# ccnor_stm32_v25-sync-unified-mini_panels.net
KiCad netlist of a schematic drawn in EAGLE
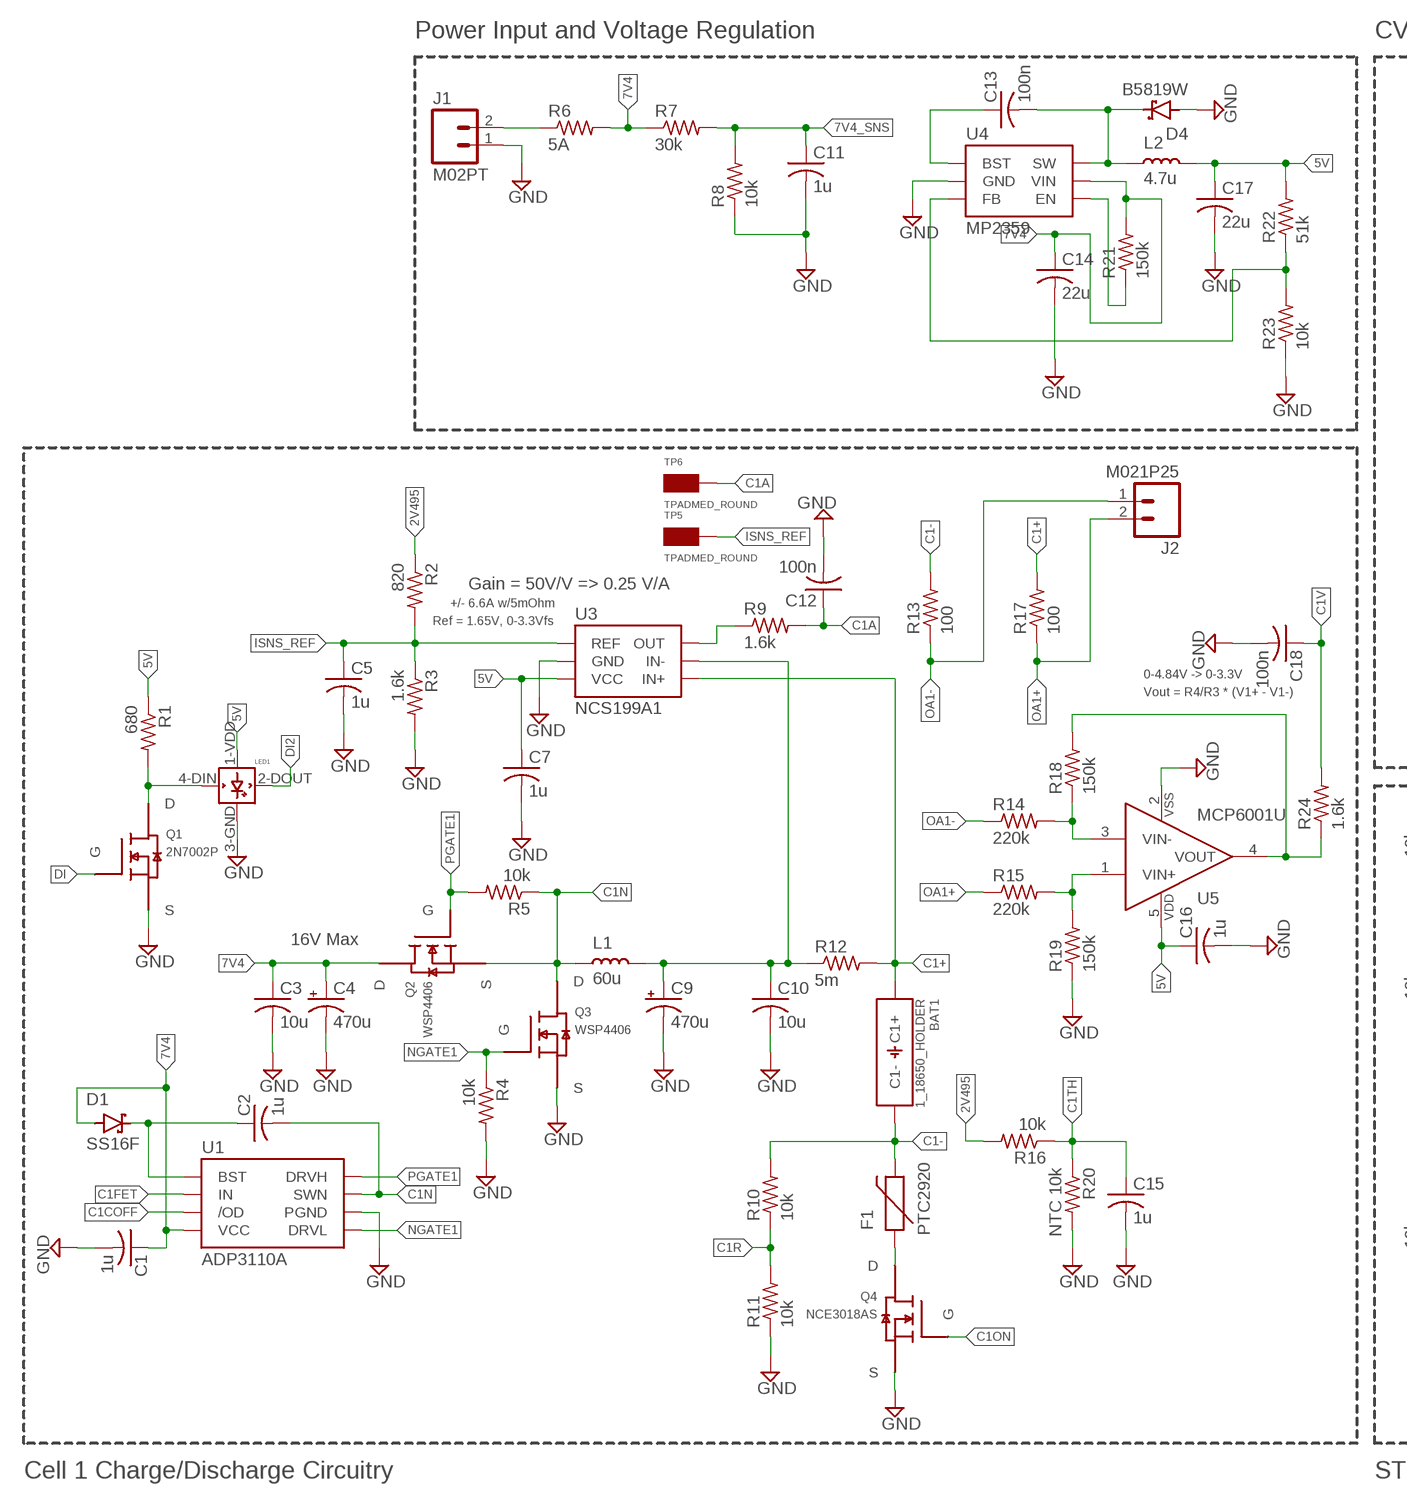
[diagram p0: schematic, sheet 1, part 1 of 3]
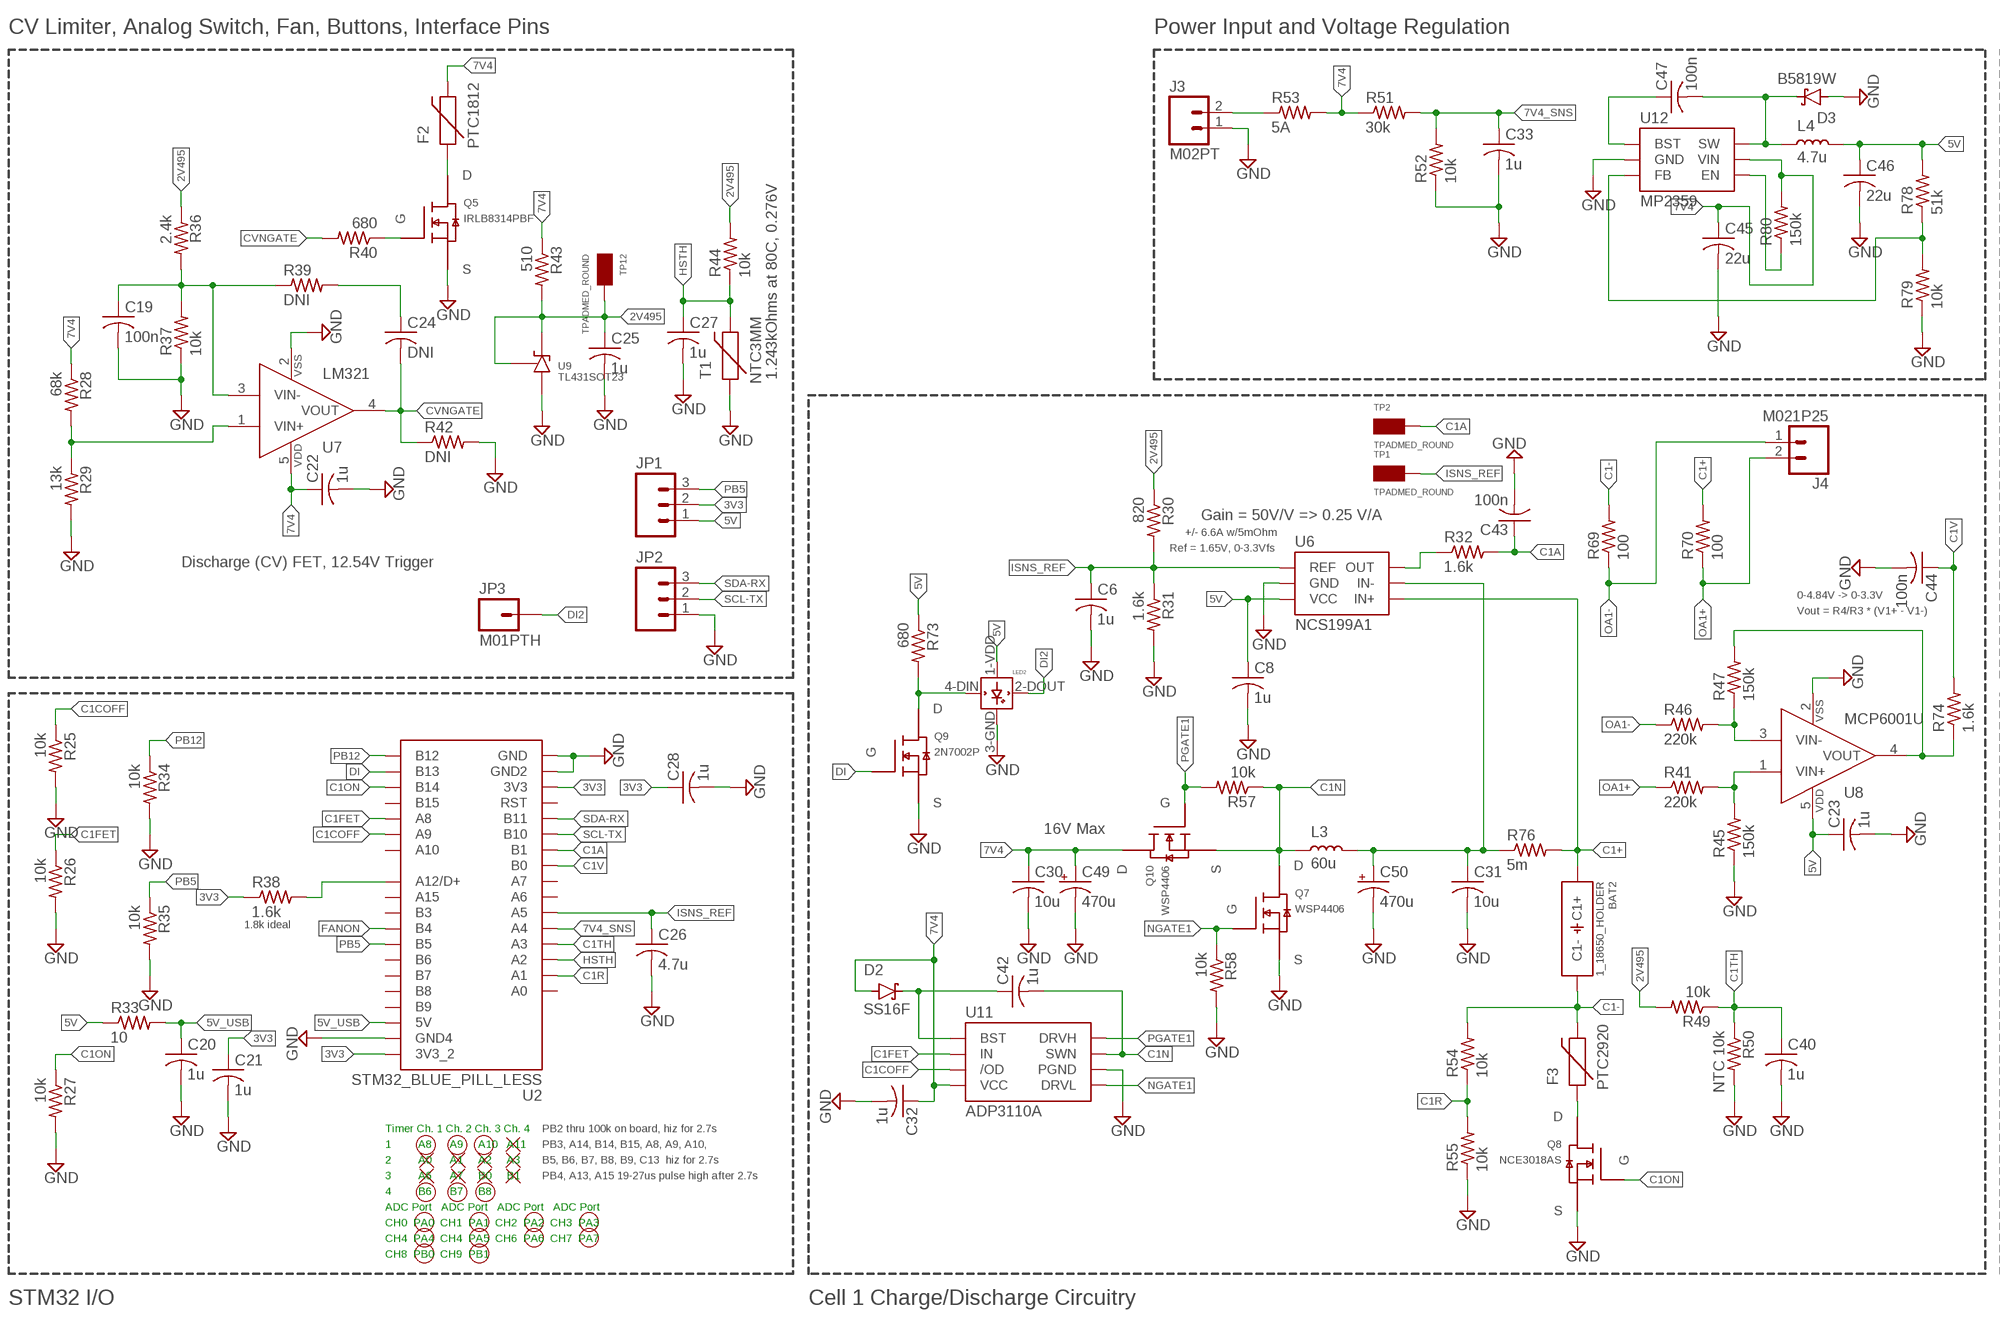
[diagram p1: schematic, sheet 1, part 2 of 3]
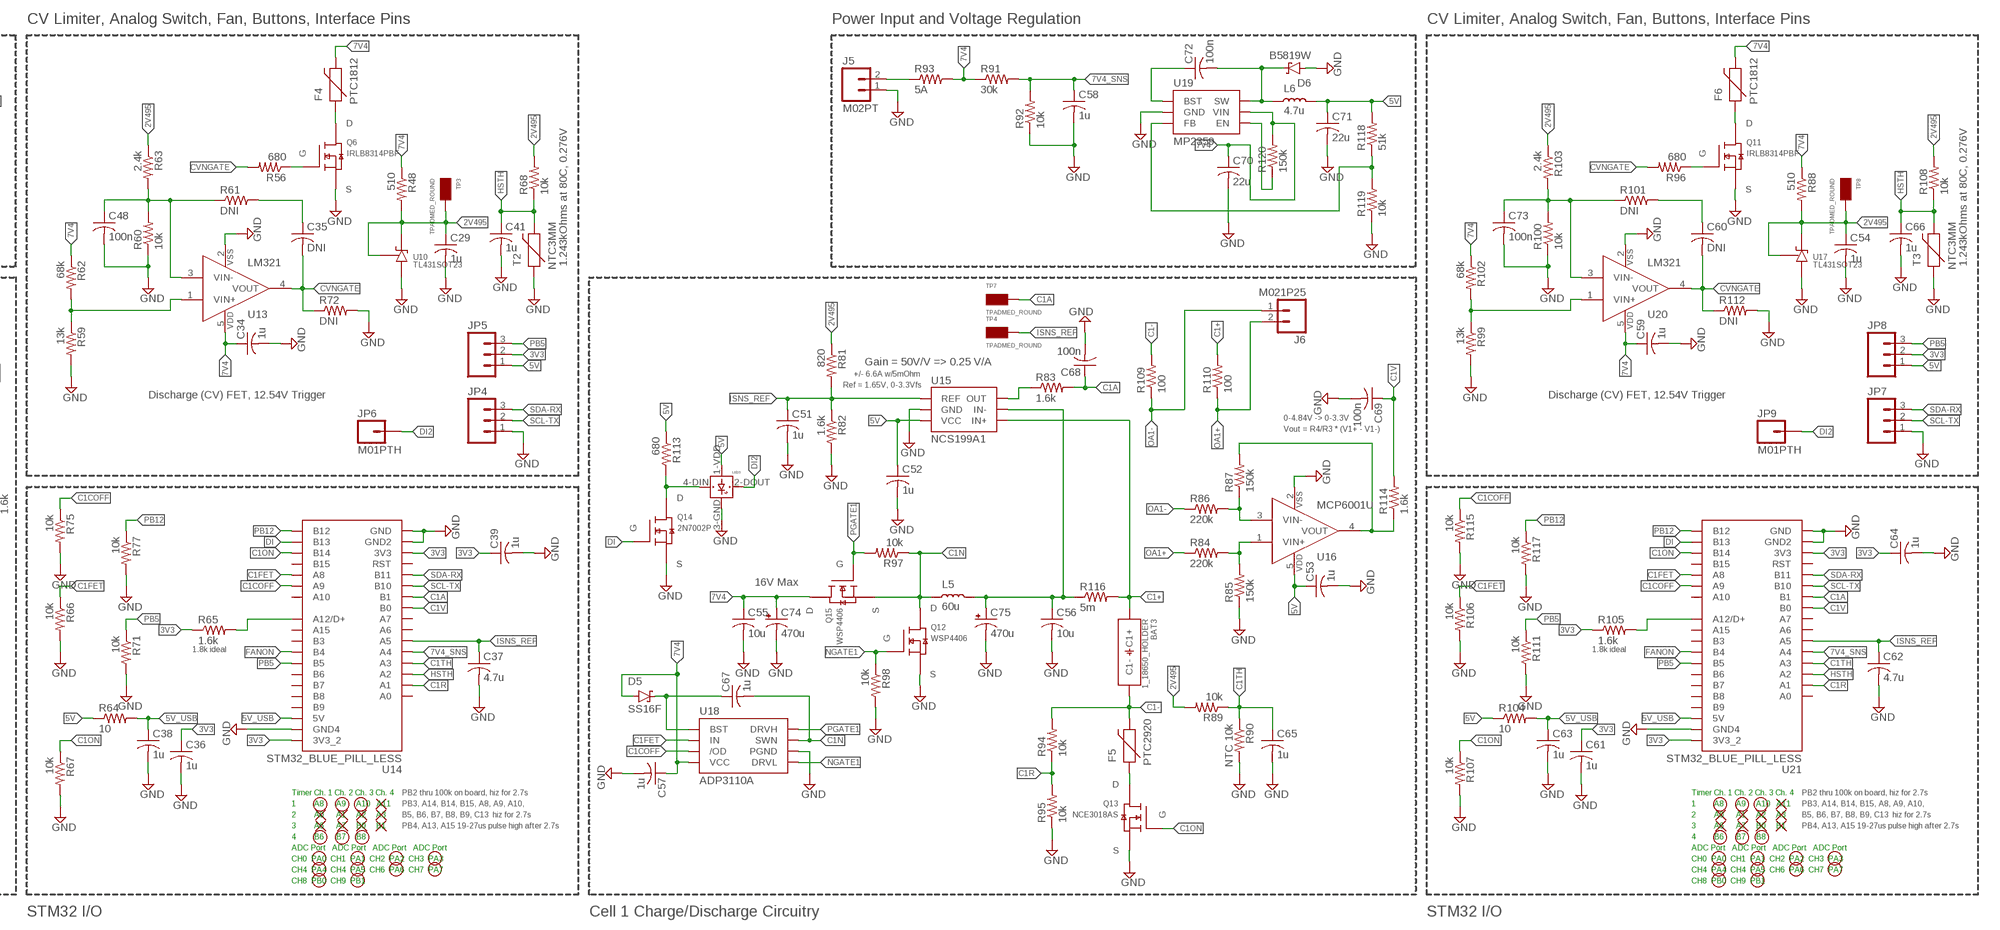
[diagram p2: schematic, sheet 1, part 3 of 3]

(export (version "E")
  (design (tool "Eeschema 10.0.6"))
  (components
    (comp (ref "BAT1")
      (value "1_18650_HOLDER")
      (footprint "eagle-import:1S_18650_SMD_NH")
      (libsource (lib "eagle-import") (part "1_18650_HOLDER"))
    )
    (comp (ref "BAT2")
      (value "1_18650_HOLDER")
      (footprint "eagle-import:1S_18650_SMD_NH")
      (libsource (lib "eagle-import") (part "1_18650_HOLDER"))
    )
    (comp (ref "BAT3")
      (value "1_18650_HOLDER")
      (footprint "eagle-import:1S_18650_SMD_NH")
      (libsource (lib "eagle-import") (part "1_18650_HOLDER"))
    )
    (comp (ref "C1")
      (value "1u")
      (footprint "eagle-import:C0402")
      (libsource (lib "eagle-import") (part "C-USC0402"))
    )
    (comp (ref "C2")
      (value "1u")
      (footprint "eagle-import:C0603")
      (libsource (lib "eagle-import") (part "C-USC0603"))
    )
    (comp (ref "C3")
      (value "10u")
      (footprint "eagle-import:C1206")
      (libsource (lib "eagle-import") (part "C-USC1206"))
    )
    (comp (ref "C4")
      (value "470u")
      (footprint "eagle-import:E2,5-7")
      (libsource (lib "eagle-import") (part "CPOL-USE2.5-7"))
    )
    (comp (ref "C5")
      (value "1u")
      (footprint "eagle-import:C0402")
      (libsource (lib "eagle-import") (part "C-USC0402"))
    )
    (comp (ref "C6")
      (value "1u")
      (footprint "eagle-import:C0402")
      (libsource (lib "eagle-import") (part "C-USC0402"))
    )
    (comp (ref "C7")
      (value "1u")
      (footprint "eagle-import:C0402")
      (libsource (lib "eagle-import") (part "C-USC0402"))
    )
    (comp (ref "C8")
      (value "1u")
      (footprint "eagle-import:C0402")
      (libsource (lib "eagle-import") (part "C-USC0402"))
    )
    (comp (ref "C9")
      (value "470u")
      (footprint "eagle-import:E2,5-7")
      (libsource (lib "eagle-import") (part "CPOL-USE2.5-7"))
    )
    (comp (ref "C10")
      (value "10u")
      (footprint "eagle-import:C1206")
      (libsource (lib "eagle-import") (part "C-USC1206"))
    )
    (comp (ref "C11")
      (value "1u")
      (footprint "eagle-import:C0402")
      (libsource (lib "eagle-import") (part "C-USC0402"))
    )
    (comp (ref "C12")
      (value "100n")
      (footprint "eagle-import:C0402")
      (libsource (lib "eagle-import") (part "C-USC0402"))
    )
    (comp (ref "C13")
      (value "100n")
      (footprint "eagle-import:C0402")
      (libsource (lib "eagle-import") (part "C-USC0402"))
    )
    (comp (ref "C14")
      (value "22u")
      (footprint "eagle-import:C0805")
      (libsource (lib "eagle-import") (part "C-USC0805"))
    )
    (comp (ref "C15")
      (value "1u")
      (footprint "eagle-import:C0402")
      (libsource (lib "eagle-import") (part "C-USC0402"))
    )
    (comp (ref "C16")
      (value "1u")
      (footprint "eagle-import:C0402")
      (libsource (lib "eagle-import") (part "C-USC0402"))
    )
    (comp (ref "C17")
      (value "22u")
      (footprint "eagle-import:C0603")
      (libsource (lib "eagle-import") (part "C-USC0603"))
    )
    (comp (ref "C18")
      (value "100n")
      (footprint "eagle-import:C0402")
      (libsource (lib "eagle-import") (part "C-USC0402"))
    )
    (comp (ref "C19")
      (value "100n")
      (footprint "eagle-import:C0402")
      (libsource (lib "eagle-import") (part "C-USC0402"))
    )
    (comp (ref "C20")
      (value "1u")
      (footprint "eagle-import:C0402")
      (libsource (lib "eagle-import") (part "C-USC0402"))
    )
    (comp (ref "C21")
      (value "1u")
      (footprint "eagle-import:C0402")
      (libsource (lib "eagle-import") (part "C-USC0402"))
    )
    (comp (ref "C22")
      (value "1u")
      (footprint "eagle-import:C0402")
      (libsource (lib "eagle-import") (part "C-USC0402"))
    )
    (comp (ref "C23")
      (value "1u")
      (footprint "eagle-import:C0402")
      (libsource (lib "eagle-import") (part "C-USC0402"))
    )
    (comp (ref "C24")
      (value "DNI")
      (footprint "eagle-import:C0402")
      (libsource (lib "eagle-import") (part "C-USC0402"))
    )
    (comp (ref "C25")
      (value "1u")
      (footprint "eagle-import:C0402")
      (libsource (lib "eagle-import") (part "C-USC0402"))
    )
    (comp (ref "C26")
      (value "4.7u")
      (footprint "eagle-import:C0402")
      (libsource (lib "eagle-import") (part "C-USC0402"))
    )
    (comp (ref "C27")
      (value "1u")
      (footprint "eagle-import:C0402")
      (libsource (lib "eagle-import") (part "C-USC0402"))
    )
    (comp (ref "C28")
      (value "1u")
      (footprint "eagle-import:C0402")
      (libsource (lib "eagle-import") (part "C-USC0402"))
    )
    (comp (ref "C29")
      (value "1u")
      (footprint "eagle-import:C0402")
      (libsource (lib "eagle-import") (part "C-USC0402"))
    )
    (comp (ref "C30")
      (value "10u")
      (footprint "eagle-import:C1206")
      (libsource (lib "eagle-import") (part "C-USC1206"))
    )
    (comp (ref "C31")
      (value "10u")
      (footprint "eagle-import:C1206")
      (libsource (lib "eagle-import") (part "C-USC1206"))
    )
    (comp (ref "C32")
      (value "1u")
      (footprint "eagle-import:C0402")
      (libsource (lib "eagle-import") (part "C-USC0402"))
    )
    (comp (ref "C33")
      (value "1u")
      (footprint "eagle-import:C0402")
      (libsource (lib "eagle-import") (part "C-USC0402"))
    )
    (comp (ref "C34")
      (value "1u")
      (footprint "eagle-import:C0402")
      (libsource (lib "eagle-import") (part "C-USC0402"))
    )
    (comp (ref "C35")
      (value "DNI")
      (footprint "eagle-import:C0402")
      (libsource (lib "eagle-import") (part "C-USC0402"))
    )
    (comp (ref "C36")
      (value "1u")
      (footprint "eagle-import:C0402")
      (libsource (lib "eagle-import") (part "C-USC0402"))
    )
    (comp (ref "C37")
      (value "4.7u")
      (footprint "eagle-import:C0402")
      (libsource (lib "eagle-import") (part "C-USC0402"))
    )
    (comp (ref "C38")
      (value "1u")
      (footprint "eagle-import:C0402")
      (libsource (lib "eagle-import") (part "C-USC0402"))
    )
    (comp (ref "C39")
      (value "1u")
      (footprint "eagle-import:C0402")
      (libsource (lib "eagle-import") (part "C-USC0402"))
    )
    (comp (ref "C40")
      (value "1u")
      (footprint "eagle-import:C0402")
      (libsource (lib "eagle-import") (part "C-USC0402"))
    )
    (comp (ref "C41")
      (value "1u")
      (footprint "eagle-import:C0402")
      (libsource (lib "eagle-import") (part "C-USC0402"))
    )
    (comp (ref "C42")
      (value "1u")
      (footprint "eagle-import:C0603")
      (libsource (lib "eagle-import") (part "C-USC0603"))
    )
    (comp (ref "C43")
      (value "100n")
      (footprint "eagle-import:C0402")
      (libsource (lib "eagle-import") (part "C-USC0402"))
    )
    (comp (ref "C44")
      (value "100n")
      (footprint "eagle-import:C0402")
      (libsource (lib "eagle-import") (part "C-USC0402"))
    )
    (comp (ref "C45")
      (value "22u")
      (footprint "eagle-import:C0805")
      (libsource (lib "eagle-import") (part "C-USC0805"))
    )
    (comp (ref "C46")
      (value "22u")
      (footprint "eagle-import:C0603")
      (libsource (lib "eagle-import") (part "C-USC0603"))
    )
    (comp (ref "C47")
      (value "100n")
      (footprint "eagle-import:C0402")
      (libsource (lib "eagle-import") (part "C-USC0402"))
    )
    (comp (ref "C48")
      (value "100n")
      (footprint "eagle-import:C0402")
      (libsource (lib "eagle-import") (part "C-USC0402"))
    )
    (comp (ref "C49")
      (value "470u")
      (footprint "eagle-import:E2,5-7")
      (libsource (lib "eagle-import") (part "CPOL-USE2.5-7"))
    )
    (comp (ref "C50")
      (value "470u")
      (footprint "eagle-import:E2,5-7")
      (libsource (lib "eagle-import") (part "CPOL-USE2.5-7"))
    )
    (comp (ref "C51")
      (value "1u")
      (footprint "eagle-import:C0402")
      (libsource (lib "eagle-import") (part "C-USC0402"))
    )
    (comp (ref "C52")
      (value "1u")
      (footprint "eagle-import:C0402")
      (libsource (lib "eagle-import") (part "C-USC0402"))
    )
    (comp (ref "C53")
      (value "1u")
      (footprint "eagle-import:C0402")
      (libsource (lib "eagle-import") (part "C-USC0402"))
    )
    (comp (ref "C54")
      (value "1u")
      (footprint "eagle-import:C0402")
      (libsource (lib "eagle-import") (part "C-USC0402"))
    )
    (comp (ref "C55")
      (value "10u")
      (footprint "eagle-import:C1206")
      (libsource (lib "eagle-import") (part "C-USC1206"))
    )
    (comp (ref "C56")
      (value "10u")
      (footprint "eagle-import:C1206")
      (libsource (lib "eagle-import") (part "C-USC1206"))
    )
    (comp (ref "C57")
      (value "1u")
      (footprint "eagle-import:C0402")
      (libsource (lib "eagle-import") (part "C-USC0402"))
    )
    (comp (ref "C58")
      (value "1u")
      (footprint "eagle-import:C0402")
      (libsource (lib "eagle-import") (part "C-USC0402"))
    )
    (comp (ref "C59")
      (value "1u")
      (footprint "eagle-import:C0402")
      (libsource (lib "eagle-import") (part "C-USC0402"))
    )
    (comp (ref "C60")
      (value "DNI")
      (footprint "eagle-import:C0402")
      (libsource (lib "eagle-import") (part "C-USC0402"))
    )
    (comp (ref "C61")
      (value "1u")
      (footprint "eagle-import:C0402")
      (libsource (lib "eagle-import") (part "C-USC0402"))
    )
    (comp (ref "C62")
      (value "4.7u")
      (footprint "eagle-import:C0402")
      (libsource (lib "eagle-import") (part "C-USC0402"))
    )
    (comp (ref "C63")
      (value "1u")
      (footprint "eagle-import:C0402")
      (libsource (lib "eagle-import") (part "C-USC0402"))
    )
    (comp (ref "C64")
      (value "1u")
      (footprint "eagle-import:C0402")
      (libsource (lib "eagle-import") (part "C-USC0402"))
    )
    (comp (ref "C65")
      (value "1u")
      (footprint "eagle-import:C0402")
      (libsource (lib "eagle-import") (part "C-USC0402"))
    )
    (comp (ref "C66")
      (value "1u")
      (footprint "eagle-import:C0402")
      (libsource (lib "eagle-import") (part "C-USC0402"))
    )
    (comp (ref "C67")
      (value "1u")
      (footprint "eagle-import:C0603")
      (libsource (lib "eagle-import") (part "C-USC0603"))
    )
    (comp (ref "C68")
      (value "100n")
      (footprint "eagle-import:C0402")
      (libsource (lib "eagle-import") (part "C-USC0402"))
    )
    (comp (ref "C69")
      (value "100n")
      (footprint "eagle-import:C0402")
      (libsource (lib "eagle-import") (part "C-USC0402"))
    )
    (comp (ref "C70")
      (value "22u")
      (footprint "eagle-import:C0805")
      (libsource (lib "eagle-import") (part "C-USC0805"))
    )
    (comp (ref "C71")
      (value "22u")
      (footprint "eagle-import:C0603")
      (libsource (lib "eagle-import") (part "C-USC0603"))
    )
    (comp (ref "C72")
      (value "100n")
      (footprint "eagle-import:C0402")
      (libsource (lib "eagle-import") (part "C-USC0402"))
    )
    (comp (ref "C73")
      (value "100n")
      (footprint "eagle-import:C0402")
      (libsource (lib "eagle-import") (part "C-USC0402"))
    )
    (comp (ref "C74")
      (value "470u")
      (footprint "eagle-import:E2,5-7")
      (libsource (lib "eagle-import") (part "CPOL-USE2.5-7"))
    )
    (comp (ref "C75")
      (value "470u")
      (footprint "eagle-import:E2,5-7")
      (libsource (lib "eagle-import") (part "CPOL-USE2.5-7"))
    )
    (comp (ref "D1")
      (value "SS16F")
      (footprint "eagle-import:SOD123")
      (libsource (lib "eagle-import") (part "DIODE_SCHOTTKYCDBM140-G"))
    )
    (comp (ref "D2")
      (value "SS16F")
      (footprint "eagle-import:SOD123")
      (libsource (lib "eagle-import") (part "DIODE_SCHOTTKYCDBM140-G"))
    )
    (comp (ref "D3")
      (value "B5819W")
      (footprint "eagle-import:SOD123W")
      (libsource (lib "eagle-import") (part "PMEG3020ER"))
    )
    (comp (ref "D4")
      (value "B5819W")
      (footprint "eagle-import:SOD123W")
      (libsource (lib "eagle-import") (part "PMEG3020ER"))
    )
    (comp (ref "D5")
      (value "SS16F")
      (footprint "eagle-import:SOD123")
      (libsource (lib "eagle-import") (part "DIODE_SCHOTTKYCDBM140-G"))
    )
    (comp (ref "D6")
      (value "B5819W")
      (footprint "eagle-import:SOD123W")
      (libsource (lib "eagle-import") (part "PMEG3020ER"))
    )
    (comp (ref "F1")
      (value "PTC2920")
      (footprint "eagle-import:2920")
      (libsource (lib "eagle-import") (part "PTC2920"))
    )
    (comp (ref "F2")
      (value "PTC1812")
      (footprint "eagle-import:1812")
      (libsource (lib "eagle-import") (part "PTC1812"))
    )
    (comp (ref "F3")
      (value "PTC2920")
      (footprint "eagle-import:2920")
      (libsource (lib "eagle-import") (part "PTC2920"))
    )
    (comp (ref "F4")
      (value "PTC1812")
      (footprint "eagle-import:1812")
      (libsource (lib "eagle-import") (part "PTC1812"))
    )
    (comp (ref "F5")
      (value "PTC2920")
      (footprint "eagle-import:2920")
      (libsource (lib "eagle-import") (part "PTC2920"))
    )
    (comp (ref "F6")
      (value "PTC1812")
      (footprint "eagle-import:1812")
      (libsource (lib "eagle-import") (part "PTC1812"))
    )
    (comp (ref "J1")
      (value "M02PT")
      (footprint "eagle-import:PHOENIXCONTACT1935161")
      (libsource (lib "eagle-import") (part "M02PT"))
    )
    (comp (ref "J2")
      (value "M021P25")
      (footprint "eagle-import:M02_1P25MM")
      (libsource (lib "eagle-import") (part "M021P25"))
    )
    (comp (ref "J3")
      (value "M02PT")
      (footprint "eagle-import:PHOENIXCONTACT1935161")
      (libsource (lib "eagle-import") (part "M02PT"))
    )
    (comp (ref "J4")
      (value "M021P25")
      (footprint "eagle-import:M02_1P25MM")
      (libsource (lib "eagle-import") (part "M021P25"))
    )
    (comp (ref "J5")
      (value "M02PT")
      (footprint "eagle-import:PHOENIXCONTACT1935161")
      (libsource (lib "eagle-import") (part "M02PT"))
    )
    (comp (ref "J6")
      (value "M021P25")
      (footprint "eagle-import:M02_1P25MM")
      (libsource (lib "eagle-import") (part "M021P25"))
    )
    (comp (ref "JP1")
      (value "M03PTH")
      (footprint "eagle-import:1X03")
      (libsource (lib "eagle-import") (part "M03PTH"))
    )
    (comp (ref "JP2")
      (value "M03PTH")
      (footprint "eagle-import:1X03")
      (libsource (lib "eagle-import") (part "M03PTH"))
    )
    (comp (ref "JP3")
      (value "M01PTH")
      (footprint "eagle-import:1X01")
      (libsource (lib "eagle-import") (part "M01PTH"))
    )
    (comp (ref "JP4")
      (value "M03PTH")
      (footprint "eagle-import:1X03")
      (libsource (lib "eagle-import") (part "M03PTH"))
    )
    (comp (ref "JP5")
      (value "M03PTH")
      (footprint "eagle-import:1X03")
      (libsource (lib "eagle-import") (part "M03PTH"))
    )
    (comp (ref "JP6")
      (value "M01PTH")
      (footprint "eagle-import:1X01")
      (libsource (lib "eagle-import") (part "M01PTH"))
    )
    (comp (ref "JP7")
      (value "M03PTH")
      (footprint "eagle-import:1X03")
      (libsource (lib "eagle-import") (part "M03PTH"))
    )
    (comp (ref "JP8")
      (value "M03PTH")
      (footprint "eagle-import:1X03")
      (libsource (lib "eagle-import") (part "M03PTH"))
    )
    (comp (ref "JP9")
      (value "M01PTH")
      (footprint "eagle-import:1X01")
      (libsource (lib "eagle-import") (part "M01PTH"))
    )
    (comp (ref "L1")
      (value "60u")
      (footprint "eagle-import:INDUCTOR_10A_8.2MMX21MM")
      (libsource (lib "eagle-import") (part "INDUCTOR10A"))
    )
    (comp (ref "L2")
      (value "4.7u")
      (footprint "eagle-import:0805")
      (libsource (lib "eagle-import") (part "INDUCTOR0805"))
    )
    (comp (ref "L3")
      (value "60u")
      (footprint "eagle-import:INDUCTOR_10A_8.2MMX21MM")
      (libsource (lib "eagle-import") (part "INDUCTOR10A"))
    )
    (comp (ref "L4")
      (value "4.7u")
      (footprint "eagle-import:0805")
      (libsource (lib "eagle-import") (part "INDUCTOR0805"))
    )
    (comp (ref "L5")
      (value "60u")
      (footprint "eagle-import:INDUCTOR_10A_8.2MMX21MM")
      (libsource (lib "eagle-import") (part "INDUCTOR10A"))
    )
    (comp (ref "L6")
      (value "4.7u")
      (footprint "eagle-import:0805")
      (libsource (lib "eagle-import") (part "INDUCTOR0805"))
    )
    (comp (ref "LED1")
      (value "WS2812B")
      (footprint "eagle-import:WS2812B")
      (libsource (lib "eagle-import") (part "WS2812B"))
    )
    (comp (ref "LED2")
      (value "WS2812B")
      (footprint "eagle-import:WS2812B")
      (libsource (lib "eagle-import") (part "WS2812B"))
    )
    (comp (ref "LED3")
      (value "WS2812B")
      (footprint "eagle-import:WS2812B")
      (libsource (lib "eagle-import") (part "WS2812B"))
    )
    (comp (ref "Q1")
      (value "2N7002P")
      (footprint "eagle-import:SOT23")
      (libsource (lib "eagle-import") (part "2N7002P"))
    )
    (comp (ref "Q2")
      (value "WSP4406")
      (footprint "eagle-import:8-SOIC")
      (libsource (lib "eagle-import") (part "N-MOSFET-SOIC8"))
    )
    (comp (ref "Q3")
      (value "WSP4406")
      (footprint "eagle-import:8-SOIC")
      (libsource (lib "eagle-import") (part "N-MOSFET-SOIC8"))
    )
    (comp (ref "Q4")
      (value "NCE3018AS")
      (footprint "eagle-import:8-SOIC")
      (libsource (lib "eagle-import") (part "N-MOSFET-SOIC8"))
    )
    (comp (ref "Q5")
      (value "IRLB8314PBF")
      (footprint "eagle-import:TO-220")
      (libsource (lib "eagle-import") (part "IRLB8314PBF"))
    )
    (comp (ref "Q6")
      (value "IRLB8314PBF")
      (footprint "eagle-import:TO-220")
      (libsource (lib "eagle-import") (part "IRLB8314PBF"))
    )
    (comp (ref "Q7")
      (value "WSP4406")
      (footprint "eagle-import:8-SOIC")
      (libsource (lib "eagle-import") (part "N-MOSFET-SOIC8"))
    )
    (comp (ref "Q8")
      (value "NCE3018AS")
      (footprint "eagle-import:8-SOIC")
      (libsource (lib "eagle-import") (part "N-MOSFET-SOIC8"))
    )
    (comp (ref "Q9")
      (value "2N7002P")
      (footprint "eagle-import:SOT23")
      (libsource (lib "eagle-import") (part "2N7002P"))
    )
    (comp (ref "Q10")
      (value "WSP4406")
      (footprint "eagle-import:8-SOIC")
      (libsource (lib "eagle-import") (part "N-MOSFET-SOIC8"))
    )
    (comp (ref "Q11")
      (value "IRLB8314PBF")
      (footprint "eagle-import:TO-220")
      (libsource (lib "eagle-import") (part "IRLB8314PBF"))
    )
    (comp (ref "Q12")
      (value "WSP4406")
      (footprint "eagle-import:8-SOIC")
      (libsource (lib "eagle-import") (part "N-MOSFET-SOIC8"))
    )
    (comp (ref "Q13")
      (value "NCE3018AS")
      (footprint "eagle-import:8-SOIC")
      (libsource (lib "eagle-import") (part "N-MOSFET-SOIC8"))
    )
    (comp (ref "Q14")
      (value "2N7002P")
      (footprint "eagle-import:SOT23")
      (libsource (lib "eagle-import") (part "2N7002P"))
    )
    (comp (ref "Q15")
      (value "WSP4406")
      (footprint "eagle-import:8-SOIC")
      (libsource (lib "eagle-import") (part "N-MOSFET-SOIC8"))
    )
    (comp (ref "R1")
      (value "680")
      (footprint "eagle-import:R0402")
      (libsource (lib "eagle-import") (part "R-US_R0402"))
    )
    (comp (ref "R2")
      (value "820")
      (footprint "eagle-import:R0402")
      (libsource (lib "eagle-import") (part "R-US_R0402"))
    )
    (comp (ref "R3")
      (value "1.6k")
      (footprint "eagle-import:R0402")
      (libsource (lib "eagle-import") (part "R-US_R0402"))
    )
    (comp (ref "R4")
      (value "10k")
      (footprint "eagle-import:R0402")
      (libsource (lib "eagle-import") (part "R-US_R0402"))
    )
    (comp (ref "R5")
      (value "10k")
      (footprint "eagle-import:R0402")
      (libsource (lib "eagle-import") (part "R-US_R0402"))
    )
    (comp (ref "R6")
      (value "5A")
      (footprint "eagle-import:R1206")
      (libsource (lib "eagle-import") (part "R-US_R1206"))
    )
    (comp (ref "R7")
      (value "30k")
      (footprint "eagle-import:R0402")
      (libsource (lib "eagle-import") (part "R-US_R0402"))
    )
    (comp (ref "R8")
      (value "10k")
      (footprint "eagle-import:R0402")
      (libsource (lib "eagle-import") (part "R-US_R0402"))
    )
    (comp (ref "R9")
      (value "1.6k")
      (footprint "eagle-import:R0402")
      (libsource (lib "eagle-import") (part "R-US_R0402"))
    )
    (comp (ref "R10")
      (value "10k")
      (footprint "eagle-import:R0402")
      (libsource (lib "eagle-import") (part "R-US_R0402"))
    )
    (comp (ref "R11")
      (value "10k")
      (footprint "eagle-import:R0402")
      (libsource (lib "eagle-import") (part "R-US_R0402"))
    )
    (comp (ref "R12")
      (value "5m")
      (footprint "eagle-import:R1206")
      (libsource (lib "eagle-import") (part "R-US_R1206"))
    )
    (comp (ref "R13")
      (value "100")
      (footprint "eagle-import:R0402")
      (libsource (lib "eagle-import") (part "R-US_R0402"))
    )
    (comp (ref "R14")
      (value "220k")
      (footprint "eagle-import:R0402")
      (libsource (lib "eagle-import") (part "R-US_R0402"))
    )
    (comp (ref "R15")
      (value "220k")
      (footprint "eagle-import:R0402")
      (libsource (lib "eagle-import") (part "R-US_R0402"))
    )
    (comp (ref "R16")
      (value "10k")
      (footprint "eagle-import:R0402")
      (libsource (lib "eagle-import") (part "R-US_R0402"))
    )
    (comp (ref "R17")
      (value "100")
      (footprint "eagle-import:R0402")
      (libsource (lib "eagle-import") (part "R-US_R0402"))
    )
    (comp (ref "R18")
      (value "150k")
      (footprint "eagle-import:R0402")
      (libsource (lib "eagle-import") (part "R-US_R0402"))
    )
    (comp (ref "R19")
      (value "150k")
      (footprint "eagle-import:R0402")
      (libsource (lib "eagle-import") (part "R-US_R0402"))
    )
    (comp (ref "R20")
      (value "NTC 10k")
      (footprint "eagle-import:R0402")
      (libsource (lib "eagle-import") (part "R-US_R0402"))
    )
    (comp (ref "R21")
      (value "150k")
      (footprint "eagle-import:R0402")
      (libsource (lib "eagle-import") (part "R-US_R0402"))
    )
    (comp (ref "R22")
      (value "51k")
      (footprint "eagle-import:R0402")
      (libsource (lib "eagle-import") (part "R-US_R0402"))
    )
    (comp (ref "R23")
      (value "10k")
      (footprint "eagle-import:R0402")
      (libsource (lib "eagle-import") (part "R-US_R0402"))
    )
    (comp (ref "R24")
      (value "1.6k")
      (footprint "eagle-import:R0402")
      (libsource (lib "eagle-import") (part "R-US_R0402"))
    )
    (comp (ref "R25")
      (value "10k")
      (footprint "eagle-import:R0402")
      (libsource (lib "eagle-import") (part "R-US_R0402"))
    )
    (comp (ref "R26")
      (value "10k")
      (footprint "eagle-import:R0402")
      (libsource (lib "eagle-import") (part "R-US_R0402"))
    )
    (comp (ref "R27")
      (value "10k")
      (footprint "eagle-import:R0402")
      (libsource (lib "eagle-import") (part "R-US_R0402"))
    )
    (comp (ref "R28")
      (value "68k")
      (footprint "eagle-import:R0402")
      (libsource (lib "eagle-import") (part "R-US_R0402"))
    )
    (comp (ref "R29")
      (value "13k")
      (footprint "eagle-import:R0402")
      (libsource (lib "eagle-import") (part "R-US_R0402"))
    )
    (comp (ref "R30")
      (value "820")
      (footprint "eagle-import:R0402")
      (libsource (lib "eagle-import") (part "R-US_R0402"))
    )
    (comp (ref "R31")
      (value "1.6k")
      (footprint "eagle-import:R0402")
      (libsource (lib "eagle-import") (part "R-US_R0402"))
    )
    (comp (ref "R32")
      (value "1.6k")
      (footprint "eagle-import:R0402")
      (libsource (lib "eagle-import") (part "R-US_R0402"))
    )
    (comp (ref "R33")
      (value "10")
      (footprint "eagle-import:R0402")
      (libsource (lib "eagle-import") (part "R-US_R0402"))
    )
    (comp (ref "R34")
      (value "10k")
      (footprint "eagle-import:R0402")
      (libsource (lib "eagle-import") (part "R-US_R0402"))
    )
    (comp (ref "R35")
      (value "10k")
      (footprint "eagle-import:R0402")
      (libsource (lib "eagle-import") (part "R-US_R0402"))
    )
    (comp (ref "R36")
      (value "2.4k")
      (footprint "eagle-import:R0402")
      (libsource (lib "eagle-import") (part "R-US_R0402"))
    )
    (comp (ref "R37")
      (value "10k")
      (footprint "eagle-import:R0402")
      (libsource (lib "eagle-import") (part "R-US_R0402"))
    )
    (comp (ref "R38")
      (value "1.6k")
      (footprint "eagle-import:R0402")
      (libsource (lib "eagle-import") (part "R-US_R0402"))
    )
    (comp (ref "R39")
      (value "DNI")
      (footprint "eagle-import:R0402")
      (libsource (lib "eagle-import") (part "R-US_R0402"))
    )
    (comp (ref "R40")
      (value "680")
      (footprint "eagle-import:R0402")
      (libsource (lib "eagle-import") (part "R-US_R0402"))
    )
    (comp (ref "R41")
      (value "220k")
      (footprint "eagle-import:R0402")
      (libsource (lib "eagle-import") (part "R-US_R0402"))
    )
    (comp (ref "R42")
      (value "DNI")
      (footprint "eagle-import:R0402")
      (libsource (lib "eagle-import") (part "R-US_R0402"))
    )
    (comp (ref "R43")
      (value "510")
      (footprint "eagle-import:R0402")
      (libsource (lib "eagle-import") (part "R-US_R0402"))
    )
    (comp (ref "R44")
      (value "10k")
      (footprint "eagle-import:R0402")
      (libsource (lib "eagle-import") (part "R-US_R0402"))
    )
    (comp (ref "R45")
      (value "150k")
      (footprint "eagle-import:R0402")
      (libsource (lib "eagle-import") (part "R-US_R0402"))
    )
    (comp (ref "R46")
      (value "220k")
      (footprint "eagle-import:R0402")
      (libsource (lib "eagle-import") (part "R-US_R0402"))
    )
    (comp (ref "R47")
      (value "150k")
      (footprint "eagle-import:R0402")
      (libsource (lib "eagle-import") (part "R-US_R0402"))
    )
    (comp (ref "R48")
      (value "510")
      (footprint "eagle-import:R0402")
      (libsource (lib "eagle-import") (part "R-US_R0402"))
    )
    (comp (ref "R49")
      (value "10k")
      (footprint "eagle-import:R0402")
      (libsource (lib "eagle-import") (part "R-US_R0402"))
    )
    (comp (ref "R50")
      (value "NTC 10k")
      (footprint "eagle-import:R0402")
      (libsource (lib "eagle-import") (part "R-US_R0402"))
    )
    (comp (ref "R51")
      (value "30k")
      (footprint "eagle-import:R0402")
      (libsource (lib "eagle-import") (part "R-US_R0402"))
    )
    (comp (ref "R52")
      (value "10k")
      (footprint "eagle-import:R0402")
      (libsource (lib "eagle-import") (part "R-US_R0402"))
    )
    (comp (ref "R53")
      (value "5A")
      (footprint "eagle-import:R1206")
      (libsource (lib "eagle-import") (part "R-US_R1206"))
    )
    (comp (ref "R54")
      (value "10k")
      (footprint "eagle-import:R0402")
      (libsource (lib "eagle-import") (part "R-US_R0402"))
    )
    (comp (ref "R55")
      (value "10k")
      (footprint "eagle-import:R0402")
      (libsource (lib "eagle-import") (part "R-US_R0402"))
    )
    (comp (ref "R56")
      (value "680")
      (footprint "eagle-import:R0402")
      (libsource (lib "eagle-import") (part "R-US_R0402"))
    )
    (comp (ref "R57")
      (value "10k")
      (footprint "eagle-import:R0402")
      (libsource (lib "eagle-import") (part "R-US_R0402"))
    )
    (comp (ref "R58")
      (value "10k")
      (footprint "eagle-import:R0402")
      (libsource (lib "eagle-import") (part "R-US_R0402"))
    )
    (comp (ref "R59")
      (value "13k")
      (footprint "eagle-import:R0402")
      (libsource (lib "eagle-import") (part "R-US_R0402"))
    )
    (comp (ref "R60")
      (value "10k")
      (footprint "eagle-import:R0402")
      (libsource (lib "eagle-import") (part "R-US_R0402"))
    )
    (comp (ref "R61")
      (value "DNI")
      (footprint "eagle-import:R0402")
      (libsource (lib "eagle-import") (part "R-US_R0402"))
    )
    (comp (ref "R62")
      (value "68k")
      (footprint "eagle-import:R0402")
      (libsource (lib "eagle-import") (part "R-US_R0402"))
    )
    (comp (ref "R63")
      (value "2.4k")
      (footprint "eagle-import:R0402")
      (libsource (lib "eagle-import") (part "R-US_R0402"))
    )
    (comp (ref "R64")
      (value "10")
      (footprint "eagle-import:R0402")
      (libsource (lib "eagle-import") (part "R-US_R0402"))
    )
    (comp (ref "R65")
      (value "1.6k")
      (footprint "eagle-import:R0402")
      (libsource (lib "eagle-import") (part "R-US_R0402"))
    )
    (comp (ref "R66")
      (value "10k")
      (footprint "eagle-import:R0402")
      (libsource (lib "eagle-import") (part "R-US_R0402"))
    )
    (comp (ref "R67")
      (value "10k")
      (footprint "eagle-import:R0402")
      (libsource (lib "eagle-import") (part "R-US_R0402"))
    )
    (comp (ref "R68")
      (value "10k")
      (footprint "eagle-import:R0402")
      (libsource (lib "eagle-import") (part "R-US_R0402"))
    )
    (comp (ref "R69")
      (value "100")
      (footprint "eagle-import:R0402")
      (libsource (lib "eagle-import") (part "R-US_R0402"))
    )
    (comp (ref "R70")
      (value "100")
      (footprint "eagle-import:R0402")
      (libsource (lib "eagle-import") (part "R-US_R0402"))
    )
    (comp (ref "R71")
      (value "10k")
      (footprint "eagle-import:R0402")
      (libsource (lib "eagle-import") (part "R-US_R0402"))
    )
    (comp (ref "R72")
      (value "DNI")
      (footprint "eagle-import:R0402")
      (libsource (lib "eagle-import") (part "R-US_R0402"))
    )
    (comp (ref "R73")
      (value "680")
      (footprint "eagle-import:R0402")
      (libsource (lib "eagle-import") (part "R-US_R0402"))
    )
    (comp (ref "R74")
      (value "1.6k")
      (footprint "eagle-import:R0402")
      (libsource (lib "eagle-import") (part "R-US_R0402"))
    )
    (comp (ref "R75")
      (value "10k")
      (footprint "eagle-import:R0402")
      (libsource (lib "eagle-import") (part "R-US_R0402"))
    )
    (comp (ref "R76")
      (value "5m")
      (footprint "eagle-import:R1206")
      (libsource (lib "eagle-import") (part "R-US_R1206"))
    )
    (comp (ref "R77")
      (value "10k")
      (footprint "eagle-import:R0402")
      (libsource (lib "eagle-import") (part "R-US_R0402"))
    )
    (comp (ref "R78")
      (value "51k")
      (footprint "eagle-import:R0402")
      (libsource (lib "eagle-import") (part "R-US_R0402"))
    )
    (comp (ref "R79")
      (value "10k")
      (footprint "eagle-import:R0402")
      (libsource (lib "eagle-import") (part "R-US_R0402"))
    )
    (comp (ref "R80")
      (value "150k")
      (footprint "eagle-import:R0402")
      (libsource (lib "eagle-import") (part "R-US_R0402"))
    )
    (comp (ref "R81")
      (value "820")
      (footprint "eagle-import:R0402")
      (libsource (lib "eagle-import") (part "R-US_R0402"))
    )
    (comp (ref "R82")
      (value "1.6k")
      (footprint "eagle-import:R0402")
      (libsource (lib "eagle-import") (part "R-US_R0402"))
    )
    (comp (ref "R83")
      (value "1.6k")
      (footprint "eagle-import:R0402")
      (libsource (lib "eagle-import") (part "R-US_R0402"))
    )
    (comp (ref "R84")
      (value "220k")
      (footprint "eagle-import:R0402")
      (libsource (lib "eagle-import") (part "R-US_R0402"))
    )
    (comp (ref "R85")
      (value "150k")
      (footprint "eagle-import:R0402")
      (libsource (lib "eagle-import") (part "R-US_R0402"))
    )
    (comp (ref "R86")
      (value "220k")
      (footprint "eagle-import:R0402")
      (libsource (lib "eagle-import") (part "R-US_R0402"))
    )
    (comp (ref "R87")
      (value "150k")
      (footprint "eagle-import:R0402")
      (libsource (lib "eagle-import") (part "R-US_R0402"))
    )
    (comp (ref "R88")
      (value "510")
      (footprint "eagle-import:R0402")
      (libsource (lib "eagle-import") (part "R-US_R0402"))
    )
    (comp (ref "R89")
      (value "10k")
      (footprint "eagle-import:R0402")
      (libsource (lib "eagle-import") (part "R-US_R0402"))
    )
    (comp (ref "R90")
      (value "NTC 10k")
      (footprint "eagle-import:R0402")
      (libsource (lib "eagle-import") (part "R-US_R0402"))
    )
    (comp (ref "R91")
      (value "30k")
      (footprint "eagle-import:R0402")
      (libsource (lib "eagle-import") (part "R-US_R0402"))
    )
    (comp (ref "R92")
      (value "10k")
      (footprint "eagle-import:R0402")
      (libsource (lib "eagle-import") (part "R-US_R0402"))
    )
    (comp (ref "R93")
      (value "5A")
      (footprint "eagle-import:R1206")
      (libsource (lib "eagle-import") (part "R-US_R1206"))
    )
    (comp (ref "R94")
      (value "10k")
      (footprint "eagle-import:R0402")
      (libsource (lib "eagle-import") (part "R-US_R0402"))
    )
    (comp (ref "R95")
      (value "10k")
      (footprint "eagle-import:R0402")
      (libsource (lib "eagle-import") (part "R-US_R0402"))
    )
    (comp (ref "R96")
      (value "680")
      (footprint "eagle-import:R0402")
      (libsource (lib "eagle-import") (part "R-US_R0402"))
    )
    (comp (ref "R97")
      (value "10k")
      (footprint "eagle-import:R0402")
      (libsource (lib "eagle-import") (part "R-US_R0402"))
    )
    (comp (ref "R98")
      (value "10k")
      (footprint "eagle-import:R0402")
      (libsource (lib "eagle-import") (part "R-US_R0402"))
    )
    (comp (ref "R99")
      (value "13k")
      (footprint "eagle-import:R0402")
      (libsource (lib "eagle-import") (part "R-US_R0402"))
    )
    (comp (ref "R100")
      (value "10k")
      (footprint "eagle-import:R0402")
      (libsource (lib "eagle-import") (part "R-US_R0402"))
    )
    (comp (ref "R101")
      (value "DNI")
      (footprint "eagle-import:R0402")
      (libsource (lib "eagle-import") (part "R-US_R0402"))
    )
    (comp (ref "R102")
      (value "68k")
      (footprint "eagle-import:R0402")
      (libsource (lib "eagle-import") (part "R-US_R0402"))
    )
    (comp (ref "R103")
      (value "2.4k")
      (footprint "eagle-import:R0402")
      (libsource (lib "eagle-import") (part "R-US_R0402"))
    )
    (comp (ref "R104")
      (value "10")
      (footprint "eagle-import:R0402")
      (libsource (lib "eagle-import") (part "R-US_R0402"))
    )
    (comp (ref "R105")
      (value "1.6k")
      (footprint "eagle-import:R0402")
      (libsource (lib "eagle-import") (part "R-US_R0402"))
    )
    (comp (ref "R106")
      (value "10k")
      (footprint "eagle-import:R0402")
      (libsource (lib "eagle-import") (part "R-US_R0402"))
    )
    (comp (ref "R107")
      (value "10k")
      (footprint "eagle-import:R0402")
      (libsource (lib "eagle-import") (part "R-US_R0402"))
    )
    (comp (ref "R108")
      (value "10k")
      (footprint "eagle-import:R0402")
      (libsource (lib "eagle-import") (part "R-US_R0402"))
    )
    (comp (ref "R109")
      (value "100")
      (footprint "eagle-import:R0402")
      (libsource (lib "eagle-import") (part "R-US_R0402"))
    )
    (comp (ref "R110")
      (value "100")
      (footprint "eagle-import:R0402")
      (libsource (lib "eagle-import") (part "R-US_R0402"))
    )
    (comp (ref "R111")
      (value "10k")
      (footprint "eagle-import:R0402")
      (libsource (lib "eagle-import") (part "R-US_R0402"))
    )
    (comp (ref "R112")
      (value "DNI")
      (footprint "eagle-import:R0402")
      (libsource (lib "eagle-import") (part "R-US_R0402"))
    )
    (comp (ref "R113")
      (value "680")
      (footprint "eagle-import:R0402")
      (libsource (lib "eagle-import") (part "R-US_R0402"))
    )
    (comp (ref "R114")
      (value "1.6k")
      (footprint "eagle-import:R0402")
      (libsource (lib "eagle-import") (part "R-US_R0402"))
    )
    (comp (ref "R115")
      (value "10k")
      (footprint "eagle-import:R0402")
      (libsource (lib "eagle-import") (part "R-US_R0402"))
    )
    (comp (ref "R116")
      (value "5m")
      (footprint "eagle-import:R1206")
      (libsource (lib "eagle-import") (part "R-US_R1206"))
    )
    (comp (ref "R117")
      (value "10k")
      (footprint "eagle-import:R0402")
      (libsource (lib "eagle-import") (part "R-US_R0402"))
    )
    (comp (ref "R118")
      (value "51k")
      (footprint "eagle-import:R0402")
      (libsource (lib "eagle-import") (part "R-US_R0402"))
    )
    (comp (ref "R119")
      (value "10k")
      (footprint "eagle-import:R0402")
      (libsource (lib "eagle-import") (part "R-US_R0402"))
    )
    (comp (ref "R120")
      (value "150k")
      (footprint "eagle-import:R0402")
      (libsource (lib "eagle-import") (part "R-US_R0402"))
    )
    (comp (ref "T1")
      (value "NTC3MM")
      (footprint "eagle-import:THERMISTOR_3MMX3MM")
      (libsource (lib "eagle-import") (part "PTCNTC3MM"))
    )
    (comp (ref "T2")
      (value "NTC3MM")
      (footprint "eagle-import:THERMISTOR_3MMX3MM")
      (libsource (lib "eagle-import") (part "PTCNTC3MM"))
    )
    (comp (ref "T3")
      (value "NTC3MM")
      (footprint "eagle-import:THERMISTOR_3MMX3MM")
      (libsource (lib "eagle-import") (part "PTCNTC3MM"))
    )
    (comp (ref "TP1")
      (value "TPADMED_ROUND")
      (footprint "eagle-import:TPAD_MED_ROUND")
      (libsource (lib "eagle-import") (part "TPADMED_ROUND"))
    )
    (comp (ref "TP2")
      (value "TPADMED_ROUND")
      (footprint "eagle-import:TPAD_MED_ROUND")
      (libsource (lib "eagle-import") (part "TPADMED_ROUND"))
    )
    (comp (ref "TP3")
      (value "TPADMED_ROUND")
      (footprint "eagle-import:TPAD_MED_ROUND")
      (libsource (lib "eagle-import") (part "TPADMED_ROUND"))
    )
    (comp (ref "TP4")
      (value "TPADMED_ROUND")
      (footprint "eagle-import:TPAD_MED_ROUND")
      (libsource (lib "eagle-import") (part "TPADMED_ROUND"))
    )
    (comp (ref "TP5")
      (value "TPADMED_ROUND")
      (footprint "eagle-import:TPAD_MED_ROUND")
      (libsource (lib "eagle-import") (part "TPADMED_ROUND"))
    )
    (comp (ref "TP6")
      (value "TPADMED_ROUND")
      (footprint "eagle-import:TPAD_MED_ROUND")
      (libsource (lib "eagle-import") (part "TPADMED_ROUND"))
    )
    (comp (ref "TP7")
      (value "TPADMED_ROUND")
      (footprint "eagle-import:TPAD_MED_ROUND")
      (libsource (lib "eagle-import") (part "TPADMED_ROUND"))
    )
    (comp (ref "TP8")
      (value "TPADMED_ROUND")
      (footprint "eagle-import:TPAD_MED_ROUND")
      (libsource (lib "eagle-import") (part "TPADMED_ROUND"))
    )
    (comp (ref "TP12")
      (value "TPADMED_ROUND")
      (footprint "eagle-import:TPAD_MED_ROUND")
      (libsource (lib "eagle-import") (part "TPADMED_ROUND"))
    )
    (comp (ref "U1")
      (value "ADP3110A")
      (footprint "eagle-import:8-SOIC")
      (libsource (lib "eagle-import") (part "ADP3110A"))
    )
    (comp (ref "U2")
      (value "STM32_BLUE_PILL_LESS")
      (footprint "eagle-import:STM32_BLUE_PILL_SMD")
      (libsource (lib "eagle-import") (part "STM32_BLUE_PILL_LESS"))
    )
    (comp (ref "U3")
      (value "NCS199A1")
      (footprint "eagle-import:SOT-363")
      (libsource (lib "eagle-import") (part "INA214"))
    )
    (comp (ref "U4")
      (value "MP2359")
      (footprint "eagle-import:SOT23-6")
      (libsource (lib "eagle-import") (part "JW5052C"))
    )
    (comp (ref "U5")
      (value "MCP6001U")
      (footprint "eagle-import:SOT23-5")
      (libsource (lib "eagle-import") (part "MCP6001U"))
    )
    (comp (ref "U6")
      (value "NCS199A1")
      (footprint "eagle-import:SOT-363")
      (libsource (lib "eagle-import") (part "INA214"))
    )
    (comp (ref "U7")
      (value "LM321")
      (footprint "eagle-import:SOT23-5")
      (libsource (lib "eagle-import") (part "LM321"))
    )
    (comp (ref "U8")
      (value "MCP6001U")
      (footprint "eagle-import:SOT23-5")
      (libsource (lib "eagle-import") (part "MCP6001U"))
    )
    (comp (ref "U9")
      (value "TL431SOT23")
      (footprint "eagle-import:SOT23")
      (libsource (lib "eagle-import") (part "TL431SOT23"))
    )
    (comp (ref "U10")
      (value "TL431SOT23")
      (footprint "eagle-import:SOT23")
      (libsource (lib "eagle-import") (part "TL431SOT23"))
    )
    (comp (ref "U11")
      (value "ADP3110A")
      (footprint "eagle-import:8-SOIC")
      (libsource (lib "eagle-import") (part "ADP3110A"))
    )
    (comp (ref "U12")
      (value "MP2359")
      (footprint "eagle-import:SOT23-6")
      (libsource (lib "eagle-import") (part "JW5052C"))
    )
    (comp (ref "U13")
      (value "LM321")
      (footprint "eagle-import:SOT23-5")
      (libsource (lib "eagle-import") (part "LM321"))
    )
    (comp (ref "U14")
      (value "STM32_BLUE_PILL_LESS")
      (footprint "eagle-import:STM32_BLUE_PILL_SMD")
      (libsource (lib "eagle-import") (part "STM32_BLUE_PILL_LESS"))
    )
    (comp (ref "U15")
      (value "NCS199A1")
      (footprint "eagle-import:SOT-363")
      (libsource (lib "eagle-import") (part "INA214"))
    )
    (comp (ref "U16")
      (value "MCP6001U")
      (footprint "eagle-import:SOT23-5")
      (libsource (lib "eagle-import") (part "MCP6001U"))
    )
    (comp (ref "U17")
      (value "TL431SOT23")
      (footprint "eagle-import:SOT23")
      (libsource (lib "eagle-import") (part "TL431SOT23"))
    )
    (comp (ref "U18")
      (value "ADP3110A")
      (footprint "eagle-import:8-SOIC")
      (libsource (lib "eagle-import") (part "ADP3110A"))
    )
    (comp (ref "U19")
      (value "MP2359")
      (footprint "eagle-import:SOT23-6")
      (libsource (lib "eagle-import") (part "JW5052C"))
    )
    (comp (ref "U20")
      (value "LM321")
      (footprint "eagle-import:SOT23-5")
      (libsource (lib "eagle-import") (part "LM321"))
    )
    (comp (ref "U21")
      (value "STM32_BLUE_PILL_LESS")
      (footprint "eagle-import:STM32_BLUE_PILL_SMD")
      (libsource (lib "eagle-import") (part "STM32_BLUE_PILL_LESS"))
    )
  )
  (nets
    (net (code "1") (name "2V495") (class "Default")
      (node (ref "C25") (pin "1") (pinfunction "1_1") (pintype "passive"))
      (node (ref "C29") (pin "1") (pinfunction "1_1") (pintype "passive"))
      (node (ref "C54") (pin "1") (pinfunction "1_1") (pintype "passive"))
      (node (ref "R103") (pin "1") (pinfunction "1_1") (pintype "passive"))
      (node (ref "R108") (pin "2") (pinfunction "2_2") (pintype "passive"))
      (node (ref "R16") (pin "2") (pinfunction "2_2") (pintype "passive"))
      (node (ref "R2") (pin "1") (pinfunction "1_1") (pintype "passive"))
      (node (ref "R30") (pin "1") (pinfunction "1_1") (pintype "passive"))
      (node (ref "R36") (pin "1") (pinfunction "1_1") (pintype "passive"))
      (node (ref "R43") (pin "2") (pinfunction "2_2") (pintype "passive"))
      (node (ref "R44") (pin "2") (pinfunction "2_2") (pintype "passive"))
      (node (ref "R48") (pin "2") (pinfunction "2_2") (pintype "passive"))
      (node (ref "R49") (pin "2") (pinfunction "2_2") (pintype "passive"))
      (node (ref "R63") (pin "1") (pinfunction "1_1") (pintype "passive"))
      (node (ref "R68") (pin "2") (pinfunction "2_2") (pintype "passive"))
      (node (ref "R81") (pin "1") (pinfunction "1_1") (pintype "passive"))
      (node (ref "R88") (pin "2") (pinfunction "2_2") (pintype "passive"))
      (node (ref "R89") (pin "2") (pinfunction "2_2") (pintype "passive"))
      (node (ref "TP12") (pin "1") (pinfunction "1_1") (pintype "bidirectional"))
      (node (ref "TP3") (pin "1") (pinfunction "1_1") (pintype "bidirectional"))
      (node (ref "TP8") (pin "1") (pinfunction "1_1") (pintype "bidirectional"))
      (node (ref "U10") (pin "1") (pinfunction "K_1") (pintype "passive"))
      (node (ref "U10") (pin "2") (pinfunction "REF_2") (pintype "passive"))
      (node (ref "U17") (pin "1") (pinfunction "K_1") (pintype "passive"))
      (node (ref "U17") (pin "2") (pinfunction "REF_2") (pintype "passive"))
      (node (ref "U9") (pin "1") (pinfunction "K_1") (pintype "passive"))
      (node (ref "U9") (pin "2") (pinfunction "REF_2") (pintype "passive"))
    )
    (net (code "2") (name "3V3") (class "Default")
      (node (ref "C21") (pin "1") (pinfunction "1_1") (pintype "passive"))
      (node (ref "C28") (pin "1") (pinfunction "1_1") (pintype "passive"))
      (node (ref "C36") (pin "1") (pinfunction "1_1") (pintype "passive"))
      (node (ref "C39") (pin "1") (pinfunction "1_1") (pintype "passive"))
      (node (ref "C61") (pin "1") (pinfunction "1_1") (pintype "passive"))
      (node (ref "C64") (pin "1") (pinfunction "1_1") (pintype "passive"))
      (node (ref "JP1") (pin "2") (pinfunction "2_2") (pintype "passive"))
      (node (ref "JP5") (pin "2") (pinfunction "2_2") (pintype "passive"))
      (node (ref "JP8") (pin "2") (pinfunction "2_2") (pintype "passive"))
      (node (ref "R105") (pin "1") (pinfunction "1_1") (pintype "passive"))
      (node (ref "R38") (pin "1") (pinfunction "1_1") (pintype "passive"))
      (node (ref "R65") (pin "1") (pinfunction "1_1") (pintype "passive"))
      (node (ref "U14") (pin "3V3") (pinfunction "3V3_3V3") (pintype "bidirectional"))
      (node (ref "U14") (pin "3V3_2") (pinfunction "3V3_2_3V3_2") (pintype "bidirectional"))
      (node (ref "U2") (pin "3V3") (pinfunction "3V3_3V3") (pintype "bidirectional"))
      (node (ref "U2") (pin "3V3_2") (pinfunction "3V3_2_3V3_2") (pintype "bidirectional"))
      (node (ref "U21") (pin "3V3") (pinfunction "3V3_3V3") (pintype "bidirectional"))
      (node (ref "U21") (pin "3V3_2") (pinfunction "3V3_2_3V3_2") (pintype "bidirectional"))
    )
    (net (code "3") (name "5V") (class "Default")
      (node (ref "C16") (pin "1") (pinfunction "1_1") (pintype "passive"))
      (node (ref "C17") (pin "1") (pinfunction "1_1") (pintype "passive"))
      (node (ref "C23") (pin "1") (pinfunction "1_1") (pintype "passive"))
      (node (ref "C46") (pin "1") (pinfunction "1_1") (pintype "passive"))
      (node (ref "C52") (pin "1") (pinfunction "1_1") (pintype "passive"))
      (node (ref "C53") (pin "1") (pinfunction "1_1") (pintype "passive"))
      (node (ref "C7") (pin "1") (pinfunction "1_1") (pintype "passive"))
      (node (ref "C71") (pin "1") (pinfunction "1_1") (pintype "passive"))
      (node (ref "C8") (pin "1") (pinfunction "1_1") (pintype "passive"))
      (node (ref "JP1") (pin "1") (pinfunction "1_1") (pintype "passive"))
      (node (ref "JP5") (pin "1") (pinfunction "1_1") (pintype "passive"))
      (node (ref "JP8") (pin "1") (pinfunction "1_1") (pintype "passive"))
      (node (ref "L2") (pin "2") (pinfunction "P$2_2") (pintype "passive"))
      (node (ref "L4") (pin "2") (pinfunction "P$2_2") (pintype "passive"))
      (node (ref "L6") (pin "2") (pinfunction "P$2_2") (pintype "passive"))
      (node (ref "LED1") (pin "1-VDD") (pinfunction "VDD_1-VDD") (pintype "bidirectional"))
      (node (ref "LED2") (pin "1-VDD") (pinfunction "VDD_1-VDD") (pintype "bidirectional"))
      (node (ref "LED3") (pin "1-VDD") (pinfunction "VDD_1-VDD") (pintype "bidirectional"))
      (node (ref "R1") (pin "1") (pinfunction "1_1") (pintype "passive"))
      (node (ref "R104") (pin "1") (pinfunction "1_1") (pintype "passive"))
      (node (ref "R113") (pin "1") (pinfunction "1_1") (pintype "passive"))
      (node (ref "R118") (pin "2") (pinfunction "2_2") (pintype "passive"))
      (node (ref "R22") (pin "2") (pinfunction "2_2") (pintype "passive"))
      (node (ref "R33") (pin "1") (pinfunction "1_1") (pintype "passive"))
      (node (ref "R64") (pin "1") (pinfunction "1_1") (pintype "passive"))
      (node (ref "R73") (pin "1") (pinfunction "1_1") (pintype "passive"))
      (node (ref "R78") (pin "2") (pinfunction "2_2") (pintype "passive"))
      (node (ref "U15") (pin "3") (pinfunction "VCC_3") (pintype "bidirectional"))
      (node (ref "U16") (pin "5") (pinfunction "VDD_5") (pintype "bidirectional"))
      (node (ref "U3") (pin "3") (pinfunction "VCC_3") (pintype "bidirectional"))
      (node (ref "U5") (pin "5") (pinfunction "VDD_5") (pintype "bidirectional"))
      (node (ref "U6") (pin "3") (pinfunction "VCC_3") (pintype "bidirectional"))
      (node (ref "U8") (pin "5") (pinfunction "VDD_5") (pintype "bidirectional"))
    )
    (net (code "4") (name "5V_USB") (class "Default")
      (node (ref "C20") (pin "1") (pinfunction "1_1") (pintype "passive"))
      (node (ref "C38") (pin "1") (pinfunction "1_1") (pintype "passive"))
      (node (ref "C63") (pin "1") (pinfunction "1_1") (pintype "passive"))
      (node (ref "R104") (pin "2") (pinfunction "2_2") (pintype "passive"))
      (node (ref "R33") (pin "2") (pinfunction "2_2") (pintype "passive"))
      (node (ref "R64") (pin "2") (pinfunction "2_2") (pintype "passive"))
      (node (ref "U14") (pin "5V") (pinfunction "5V_5V") (pintype "bidirectional"))
      (node (ref "U2") (pin "5V") (pinfunction "5V_5V") (pintype "bidirectional"))
      (node (ref "U21") (pin "5V") (pinfunction "5V_5V") (pintype "bidirectional"))
    )
    (net (code "5") (name "7V4") (class "Default")
      (node (ref "C1") (pin "1") (pinfunction "1_1") (pintype "passive"))
      (node (ref "C14") (pin "1") (pinfunction "1_1") (pintype "passive"))
      (node (ref "C22") (pin "1") (pinfunction "1_1") (pintype "passive"))
      (node (ref "C3") (pin "1") (pinfunction "1_1") (pintype "passive"))
      (node (ref "C30") (pin "1") (pinfunction "1_1") (pintype "passive"))
      (node (ref "C32") (pin "1") (pinfunction "1_1") (pintype "passive"))
      (node (ref "C34") (pin "1") (pinfunction "1_1") (pintype "passive"))
      (node (ref "C4") (pin "+") (pinfunction "+_+") (pintype "passive"))
      (node (ref "C45") (pin "1") (pinfunction "1_1") (pintype "passive"))
      (node (ref "C49") (pin "+") (pinfunction "+_+") (pintype "passive"))
      (node (ref "C55") (pin "1") (pinfunction "1_1") (pintype "passive"))
      (node (ref "C57") (pin "1") (pinfunction "1_1") (pintype "passive"))
      (node (ref "C59") (pin "1") (pinfunction "1_1") (pintype "passive"))
      (node (ref "C70") (pin "1") (pinfunction "1_1") (pintype "passive"))
      (node (ref "C74") (pin "+") (pinfunction "+_+") (pintype "passive"))
      (node (ref "D1") (pin "A") (pinfunction "ANODE_A") (pintype "passive"))
      (node (ref "D2") (pin "A") (pinfunction "ANODE_A") (pintype "passive"))
      (node (ref "D5") (pin "A") (pinfunction "ANODE_A") (pintype "passive"))
      (node (ref "F2") (pin "2") (pinfunction "2_2") (pintype "bidirectional"))
      (node (ref "F4") (pin "2") (pinfunction "2_2") (pintype "bidirectional"))
      (node (ref "F6") (pin "2") (pinfunction "2_2") (pintype "bidirectional"))
      (node (ref "Q10") (pin "5") (pinfunction "D_5") (pintype "bidirectional"))
      (node (ref "Q10") (pin "6") (pinfunction "D_6") (pintype "bidirectional"))
      (node (ref "Q10") (pin "7") (pinfunction "D_7") (pintype "bidirectional"))
      (node (ref "Q10") (pin "8") (pinfunction "D_8") (pintype "bidirectional"))
      (node (ref "Q15") (pin "5") (pinfunction "D_5") (pintype "bidirectional"))
      (node (ref "Q15") (pin "6") (pinfunction "D_6") (pintype "bidirectional"))
      (node (ref "Q15") (pin "7") (pinfunction "D_7") (pintype "bidirectional"))
      (node (ref "Q15") (pin "8") (pinfunction "D_8") (pintype "bidirectional"))
      (node (ref "Q2") (pin "5") (pinfunction "D_5") (pintype "bidirectional"))
      (node (ref "Q2") (pin "6") (pinfunction "D_6") (pintype "bidirectional"))
      (node (ref "Q2") (pin "7") (pinfunction "D_7") (pintype "bidirectional"))
      (node (ref "Q2") (pin "8") (pinfunction "D_8") (pintype "bidirectional"))
      (node (ref "R102") (pin "1") (pinfunction "1_1") (pintype "passive"))
      (node (ref "R120") (pin "2") (pinfunction "2_2") (pintype "passive"))
      (node (ref "R21") (pin "2") (pinfunction "2_2") (pintype "passive"))
      (node (ref "R28") (pin "1") (pinfunction "1_1") (pintype "passive"))
      (node (ref "R43") (pin "1") (pinfunction "1_1") (pintype "passive"))
      (node (ref "R48") (pin "1") (pinfunction "1_1") (pintype "passive"))
      (node (ref "R51") (pin "1") (pinfunction "1_1") (pintype "passive"))
      (node (ref "R53") (pin "2") (pinfunction "2_2") (pintype "passive"))
      (node (ref "R6") (pin "2") (pinfunction "2_2") (pintype "passive"))
      (node (ref "R62") (pin "1") (pinfunction "1_1") (pintype "passive"))
      (node (ref "R7") (pin "1") (pinfunction "1_1") (pintype "passive"))
      (node (ref "R80") (pin "2") (pinfunction "2_2") (pintype "passive"))
      (node (ref "R88") (pin "1") (pinfunction "1_1") (pintype "passive"))
      (node (ref "R91") (pin "1") (pinfunction "1_1") (pintype "passive"))
      (node (ref "R93") (pin "2") (pinfunction "2_2") (pintype "passive"))
      (node (ref "U1") (pin "4") (pinfunction "VCC_4") (pintype "bidirectional"))
      (node (ref "U11") (pin "4") (pinfunction "VCC_4") (pintype "bidirectional"))
      (node (ref "U12") (pin "5") (pinfunction "VIN_5") (pintype "bidirectional"))
      (node (ref "U13") (pin "5") (pinfunction "VDD_5") (pintype "bidirectional"))
      (node (ref "U18") (pin "4") (pinfunction "VCC_4") (pintype "bidirectional"))
      (node (ref "U19") (pin "5") (pinfunction "VIN_5") (pintype "bidirectional"))
      (node (ref "U20") (pin "5") (pinfunction "VDD_5") (pintype "bidirectional"))
      (node (ref "U4") (pin "5") (pinfunction "VIN_5") (pintype "bidirectional"))
      (node (ref "U7") (pin "5") (pinfunction "VDD_5") (pintype "bidirectional"))
    )
    (net (code "6") (name "7V4_SNS") (class "Default")
      (node (ref "C11") (pin "1") (pinfunction "1_1") (pintype "passive"))
      (node (ref "C33") (pin "1") (pinfunction "1_1") (pintype "passive"))
      (node (ref "C58") (pin "1") (pinfunction "1_1") (pintype "passive"))
      (node (ref "R51") (pin "2") (pinfunction "2_2") (pintype "passive"))
      (node (ref "R52") (pin "2") (pinfunction "2_2") (pintype "passive"))
      (node (ref "R7") (pin "2") (pinfunction "2_2") (pintype "passive"))
      (node (ref "R8") (pin "2") (pinfunction "2_2") (pintype "passive"))
      (node (ref "R91") (pin "2") (pinfunction "2_2") (pintype "passive"))
      (node (ref "R92") (pin "2") (pinfunction "2_2") (pintype "passive"))
      (node (ref "U14") (pin "A4") (pinfunction "A4_A4") (pintype "bidirectional"))
      (node (ref "U2") (pin "A4") (pinfunction "A4_A4") (pintype "bidirectional"))
      (node (ref "U21") (pin "A4") (pinfunction "A4_A4") (pintype "bidirectional"))
    )
    (net (code "7") (name "C1+") (class "Default")
      (node (ref "BAT1") (pin "1+") (pinfunction "C1+_1+") (pintype "bidirectional"))
      (node (ref "BAT2") (pin "1+") (pinfunction "C1+_1+") (pintype "bidirectional"))
      (node (ref "BAT3") (pin "1+") (pinfunction "C1+_1+") (pintype "bidirectional"))
      (node (ref "R110") (pin "2") (pinfunction "2_2") (pintype "passive"))
      (node (ref "R116") (pin "2") (pinfunction "2_2") (pintype "passive"))
      (node (ref "R12") (pin "2") (pinfunction "2_2") (pintype "passive"))
      (node (ref "R17") (pin "2") (pinfunction "2_2") (pintype "passive"))
      (node (ref "R70") (pin "2") (pinfunction "2_2") (pintype "passive"))
      (node (ref "R76") (pin "2") (pinfunction "2_2") (pintype "passive"))
      (node (ref "U15") (pin "4") (pinfunction "IN+_4") (pintype "bidirectional"))
      (node (ref "U3") (pin "4") (pinfunction "IN+_4") (pintype "bidirectional"))
      (node (ref "U6") (pin "4") (pinfunction "IN+_4") (pintype "bidirectional"))
    )
    (net (code "8") (name "C1-") (class "Default")
      (node (ref "BAT1") (pin "1-") (pinfunction "C1-_1-") (pintype "bidirectional"))
      (node (ref "BAT2") (pin "1-") (pinfunction "C1-_1-") (pintype "bidirectional"))
      (node (ref "BAT3") (pin "1-") (pinfunction "C1-_1-") (pintype "bidirectional"))
      (node (ref "F1") (pin "K") (pinfunction "2_K") (pintype "bidirectional"))
      (node (ref "F3") (pin "K") (pinfunction "2_K") (pintype "bidirectional"))
      (node (ref "F5") (pin "K") (pinfunction "2_K") (pintype "bidirectional"))
      (node (ref "R10") (pin "2") (pinfunction "2_2") (pintype "passive"))
      (node (ref "R109") (pin "2") (pinfunction "2_2") (pintype "passive"))
      (node (ref "R13") (pin "2") (pinfunction "2_2") (pintype "passive"))
      (node (ref "R54") (pin "2") (pinfunction "2_2") (pintype "passive"))
      (node (ref "R69") (pin "2") (pinfunction "2_2") (pintype "passive"))
      (node (ref "R94") (pin "2") (pinfunction "2_2") (pintype "passive"))
    )
    (net (code "9") (name "C1A") (class "Default")
      (node (ref "C12") (pin "1") (pinfunction "1_1") (pintype "passive"))
      (node (ref "C43") (pin "1") (pinfunction "1_1") (pintype "passive"))
      (node (ref "C68") (pin "1") (pinfunction "1_1") (pintype "passive"))
      (node (ref "R32") (pin "2") (pinfunction "2_2") (pintype "passive"))
      (node (ref "R83") (pin "2") (pinfunction "2_2") (pintype "passive"))
      (node (ref "R9") (pin "2") (pinfunction "2_2") (pintype "passive"))
      (node (ref "TP2") (pin "1") (pinfunction "1_1") (pintype "bidirectional"))
      (node (ref "TP6") (pin "1") (pinfunction "1_1") (pintype "bidirectional"))
      (node (ref "TP7") (pin "1") (pinfunction "1_1") (pintype "bidirectional"))
      (node (ref "U14") (pin "B1") (pinfunction "B1_B1") (pintype "bidirectional"))
      (node (ref "U2") (pin "B1") (pinfunction "B1_B1") (pintype "bidirectional"))
      (node (ref "U21") (pin "B1") (pinfunction "B1_B1") (pintype "bidirectional"))
    )
    (net (code "10") (name "C1COFF") (class "Default")
      (node (ref "R115") (pin "1") (pinfunction "1_1") (pintype "passive"))
      (node (ref "R25") (pin "1") (pinfunction "1_1") (pintype "passive"))
      (node (ref "R75") (pin "1") (pinfunction "1_1") (pintype "passive"))
      (node (ref "U1") (pin "3") (pinfunction "/OD_3") (pintype "bidirectional"))
      (node (ref "U11") (pin "3") (pinfunction "/OD_3") (pintype "bidirectional"))
      (node (ref "U14") (pin "A9") (pinfunction "A9_A9") (pintype "bidirectional"))
      (node (ref "U18") (pin "3") (pinfunction "/OD_3") (pintype "bidirectional"))
      (node (ref "U2") (pin "A9") (pinfunction "A9_A9") (pintype "bidirectional"))
      (node (ref "U21") (pin "A9") (pinfunction "A9_A9") (pintype "bidirectional"))
    )
    (net (code "11") (name "C1FET") (class "Default")
      (node (ref "R106") (pin "1") (pinfunction "1_1") (pintype "passive"))
      (node (ref "R26") (pin "1") (pinfunction "1_1") (pintype "passive"))
      (node (ref "R66") (pin "1") (pinfunction "1_1") (pintype "passive"))
      (node (ref "U1") (pin "2") (pinfunction "IN_2") (pintype "bidirectional"))
      (node (ref "U11") (pin "2") (pinfunction "IN_2") (pintype "bidirectional"))
      (node (ref "U14") (pin "A8") (pinfunction "A8_A8") (pintype "bidirectional"))
      (node (ref "U18") (pin "2") (pinfunction "IN_2") (pintype "bidirectional"))
      (node (ref "U2") (pin "A8") (pinfunction "A8_A8") (pintype "bidirectional"))
      (node (ref "U21") (pin "A8") (pinfunction "A8_A8") (pintype "bidirectional"))
    )
    (net (code "12") (name "C1N") (class "Default")
      (node (ref "C2") (pin "2") (pinfunction "2_2") (pintype "passive"))
      (node (ref "C42") (pin "2") (pinfunction "2_2") (pintype "passive"))
      (node (ref "C67") (pin "2") (pinfunction "2_2") (pintype "passive"))
      (node (ref "L1") (pin "P$1") (pinfunction "P$1_P$1") (pintype "passive"))
      (node (ref "L3") (pin "P$1") (pinfunction "P$1_P$1") (pintype "passive"))
      (node (ref "L5") (pin "P$1") (pinfunction "P$1_P$1") (pintype "passive"))
      (node (ref "Q10") (pin "1") (pinfunction "S_1") (pintype "bidirectional"))
      (node (ref "Q10") (pin "2") (pinfunction "S_2") (pintype "bidirectional"))
      (node (ref "Q10") (pin "3") (pinfunction "S_3") (pintype "bidirectional"))
      (node (ref "Q12") (pin "5") (pinfunction "D_5") (pintype "bidirectional"))
      (node (ref "Q12") (pin "6") (pinfunction "D_6") (pintype "bidirectional"))
      (node (ref "Q12") (pin "7") (pinfunction "D_7") (pintype "bidirectional"))
      (node (ref "Q12") (pin "8") (pinfunction "D_8") (pintype "bidirectional"))
      (node (ref "Q15") (pin "1") (pinfunction "S_1") (pintype "bidirectional"))
      (node (ref "Q15") (pin "2") (pinfunction "S_2") (pintype "bidirectional"))
      (node (ref "Q15") (pin "3") (pinfunction "S_3") (pintype "bidirectional"))
      (node (ref "Q2") (pin "1") (pinfunction "S_1") (pintype "bidirectional"))
      (node (ref "Q2") (pin "2") (pinfunction "S_2") (pintype "bidirectional"))
      (node (ref "Q2") (pin "3") (pinfunction "S_3") (pintype "bidirectional"))
      (node (ref "Q3") (pin "5") (pinfunction "D_5") (pintype "bidirectional"))
      (node (ref "Q3") (pin "6") (pinfunction "D_6") (pintype "bidirectional"))
      (node (ref "Q3") (pin "7") (pinfunction "D_7") (pintype "bidirectional"))
      (node (ref "Q3") (pin "8") (pinfunction "D_8") (pintype "bidirectional"))
      (node (ref "Q7") (pin "5") (pinfunction "D_5") (pintype "bidirectional"))
      (node (ref "Q7") (pin "6") (pinfunction "D_6") (pintype "bidirectional"))
      (node (ref "Q7") (pin "7") (pinfunction "D_7") (pintype "bidirectional"))
      (node (ref "Q7") (pin "8") (pinfunction "D_8") (pintype "bidirectional"))
      (node (ref "R5") (pin "1") (pinfunction "1_1") (pintype "passive"))
      (node (ref "R57") (pin "1") (pinfunction "1_1") (pintype "passive"))
      (node (ref "R97") (pin "1") (pinfunction "1_1") (pintype "passive"))
      (node (ref "U1") (pin "7") (pinfunction "SWN_7") (pintype "bidirectional"))
      (node (ref "U11") (pin "7") (pinfunction "SWN_7") (pintype "bidirectional"))
      (node (ref "U18") (pin "7") (pinfunction "SWN_7") (pintype "bidirectional"))
    )
    (net (code "13") (name "C1ON") (class "Default")
      (node (ref "Q13") (pin "4") (pinfunction "G_4") (pintype "bidirectional"))
      (node (ref "Q4") (pin "4") (pinfunction "G_4") (pintype "bidirectional"))
      (node (ref "Q8") (pin "4") (pinfunction "G_4") (pintype "bidirectional"))
      (node (ref "R107") (pin "1") (pinfunction "1_1") (pintype "passive"))
      (node (ref "R27") (pin "1") (pinfunction "1_1") (pintype "passive"))
      (node (ref "R67") (pin "1") (pinfunction "1_1") (pintype "passive"))
      (node (ref "U14") (pin "B14") (pinfunction "B14_B14") (pintype "bidirectional"))
      (node (ref "U2") (pin "B14") (pinfunction "B14_B14") (pintype "bidirectional"))
      (node (ref "U21") (pin "B14") (pinfunction "B14_B14") (pintype "bidirectional"))
    )
    (net (code "14") (name "C1R") (class "Default")
      (node (ref "R10") (pin "1") (pinfunction "1_1") (pintype "passive"))
      (node (ref "R11") (pin "2") (pinfunction "2_2") (pintype "passive"))
      (node (ref "R54") (pin "1") (pinfunction "1_1") (pintype "passive"))
      (node (ref "R55") (pin "2") (pinfunction "2_2") (pintype "passive"))
      (node (ref "R94") (pin "1") (pinfunction "1_1") (pintype "passive"))
      (node (ref "R95") (pin "2") (pinfunction "2_2") (pintype "passive"))
      (node (ref "U14") (pin "A1") (pinfunction "A1_A1") (pintype "bidirectional"))
      (node (ref "U2") (pin "A1") (pinfunction "A1_A1") (pintype "bidirectional"))
      (node (ref "U21") (pin "A1") (pinfunction "A1_A1") (pintype "bidirectional"))
    )
    (net (code "15") (name "C1TH") (class "Default")
      (node (ref "C15") (pin "1") (pinfunction "1_1") (pintype "passive"))
      (node (ref "C40") (pin "1") (pinfunction "1_1") (pintype "passive"))
      (node (ref "C65") (pin "1") (pinfunction "1_1") (pintype "passive"))
      (node (ref "R16") (pin "1") (pinfunction "1_1") (pintype "passive"))
      (node (ref "R20") (pin "1") (pinfunction "1_1") (pintype "passive"))
      (node (ref "R49") (pin "1") (pinfunction "1_1") (pintype "passive"))
      (node (ref "R50") (pin "1") (pinfunction "1_1") (pintype "passive"))
      (node (ref "R89") (pin "1") (pinfunction "1_1") (pintype "passive"))
      (node (ref "R90") (pin "1") (pinfunction "1_1") (pintype "passive"))
      (node (ref "U14") (pin "A3") (pinfunction "A3_A3") (pintype "bidirectional"))
      (node (ref "U2") (pin "A3") (pinfunction "A3_A3") (pintype "bidirectional"))
      (node (ref "U21") (pin "A3") (pinfunction "A3_A3") (pintype "bidirectional"))
    )
    (net (code "16") (name "C1V") (class "Default")
      (node (ref "C18") (pin "1") (pinfunction "1_1") (pintype "passive"))
      (node (ref "C44") (pin "1") (pinfunction "1_1") (pintype "passive"))
      (node (ref "C69") (pin "1") (pinfunction "1_1") (pintype "passive"))
      (node (ref "R114") (pin "2") (pinfunction "2_2") (pintype "passive"))
      (node (ref "R24") (pin "2") (pinfunction "2_2") (pintype "passive"))
      (node (ref "R74") (pin "2") (pinfunction "2_2") (pintype "passive"))
      (node (ref "U14") (pin "B0") (pinfunction "B0_B0") (pintype "bidirectional"))
      (node (ref "U2") (pin "B0") (pinfunction "B0_B0") (pintype "bidirectional"))
      (node (ref "U21") (pin "B0") (pinfunction "B0_B0") (pintype "bidirectional"))
    )
    (net (code "17") (name "CVNGATE") (class "Default")
      (node (ref "C24") (pin "2") (pinfunction "2_2") (pintype "passive"))
      (node (ref "C35") (pin "2") (pinfunction "2_2") (pintype "passive"))
      (node (ref "C60") (pin "2") (pinfunction "2_2") (pintype "passive"))
      (node (ref "R112") (pin "1") (pinfunction "1_1") (pintype "passive"))
      (node (ref "R40") (pin "2") (pinfunction "2_2") (pintype "passive"))
      (node (ref "R42") (pin "1") (pinfunction "1_1") (pintype "passive"))
      (node (ref "R56") (pin "2") (pinfunction "2_2") (pintype "passive"))
      (node (ref "R72") (pin "1") (pinfunction "1_1") (pintype "passive"))
      (node (ref "R96") (pin "2") (pinfunction "2_2") (pintype "passive"))
      (node (ref "U13") (pin "4") (pinfunction "VOUT_4") (pintype "bidirectional"))
      (node (ref "U20") (pin "4") (pinfunction "VOUT_4") (pintype "bidirectional"))
      (node (ref "U7") (pin "4") (pinfunction "VOUT_4") (pintype "bidirectional"))
    )
    (net (code "18") (name "DI") (class "Default")
      (node (ref "Q1") (pin "1") (pinfunction "G_1") (pintype "bidirectional"))
      (node (ref "Q14") (pin "1") (pinfunction "G_1") (pintype "bidirectional"))
      (node (ref "Q9") (pin "1") (pinfunction "G_1") (pintype "bidirectional"))
      (node (ref "U14") (pin "B13") (pinfunction "B13_B13") (pintype "bidirectional"))
      (node (ref "U2") (pin "B13") (pinfunction "B13_B13") (pintype "bidirectional"))
      (node (ref "U21") (pin "B13") (pinfunction "B13_B13") (pintype "bidirectional"))
    )
    (net (code "19") (name "DI2") (class "Default")
      (node (ref "JP3") (pin "1") (pinfunction "1_1") (pintype "passive"))
      (node (ref "JP6") (pin "1") (pinfunction "1_1") (pintype "passive"))
      (node (ref "JP9") (pin "1") (pinfunction "1_1") (pintype "passive"))
      (node (ref "LED1") (pin "2-DOUT") (pinfunction "DOUT_2-DOUT") (pintype "output"))
      (node (ref "LED2") (pin "2-DOUT") (pinfunction "DOUT_2-DOUT") (pintype "output"))
      (node (ref "LED3") (pin "2-DOUT") (pinfunction "DOUT_2-DOUT") (pintype "output"))
    )
    (net (code "20") (name "FANON") (class "Default")
      (node (ref "U14") (pin "B4") (pinfunction "B4_B4") (pintype "bidirectional"))
      (node (ref "U2") (pin "B4") (pinfunction "B4_B4") (pintype "bidirectional"))
      (node (ref "U21") (pin "B4") (pinfunction "B4_B4") (pintype "bidirectional"))
    )
    (net (code "21") (name "GND") (class "Default")
      (node (ref "C1") (pin "2") (pinfunction "2_2") (pintype "passive"))
      (node (ref "C10") (pin "2") (pinfunction "2_2") (pintype "passive"))
      (node (ref "C11") (pin "2") (pinfunction "2_2") (pintype "passive"))
      (node (ref "C12") (pin "2") (pinfunction "2_2") (pintype "passive"))
      (node (ref "C14") (pin "2") (pinfunction "2_2") (pintype "passive"))
      (node (ref "C15") (pin "2") (pinfunction "2_2") (pintype "passive"))
      (node (ref "C16") (pin "2") (pinfunction "2_2") (pintype "passive"))
      (node (ref "C17") (pin "2") (pinfunction "2_2") (pintype "passive"))
      (node (ref "C18") (pin "2") (pinfunction "2_2") (pintype "passive"))
      (node (ref "C19") (pin "2") (pinfunction "2_2") (pintype "passive"))
      (node (ref "C20") (pin "2") (pinfunction "2_2") (pintype "passive"))
      (node (ref "C21") (pin "2") (pinfunction "2_2") (pintype "passive"))
      (node (ref "C22") (pin "2") (pinfunction "2_2") (pintype "passive"))
      (node (ref "C23") (pin "2") (pinfunction "2_2") (pintype "passive"))
      (node (ref "C25") (pin "2") (pinfunction "2_2") (pintype "passive"))
      (node (ref "C26") (pin "2") (pinfunction "2_2") (pintype "passive"))
      (node (ref "C27") (pin "2") (pinfunction "2_2") (pintype "passive"))
      (node (ref "C28") (pin "2") (pinfunction "2_2") (pintype "passive"))
      (node (ref "C29") (pin "2") (pinfunction "2_2") (pintype "passive"))
      (node (ref "C3") (pin "2") (pinfunction "2_2") (pintype "passive"))
      (node (ref "C30") (pin "2") (pinfunction "2_2") (pintype "passive"))
      (node (ref "C31") (pin "2") (pinfunction "2_2") (pintype "passive"))
      (node (ref "C32") (pin "2") (pinfunction "2_2") (pintype "passive"))
      (node (ref "C33") (pin "2") (pinfunction "2_2") (pintype "passive"))
      (node (ref "C34") (pin "2") (pinfunction "2_2") (pintype "passive"))
      (node (ref "C36") (pin "2") (pinfunction "2_2") (pintype "passive"))
      (node (ref "C37") (pin "2") (pinfunction "2_2") (pintype "passive"))
      (node (ref "C38") (pin "2") (pinfunction "2_2") (pintype "passive"))
      (node (ref "C39") (pin "2") (pinfunction "2_2") (pintype "passive"))
      (node (ref "C4") (pin "-") (pinfunction "-_-") (pintype "passive"))
      (node (ref "C40") (pin "2") (pinfunction "2_2") (pintype "passive"))
      (node (ref "C41") (pin "2") (pinfunction "2_2") (pintype "passive"))
      (node (ref "C43") (pin "2") (pinfunction "2_2") (pintype "passive"))
      (node (ref "C44") (pin "2") (pinfunction "2_2") (pintype "passive"))
      (node (ref "C45") (pin "2") (pinfunction "2_2") (pintype "passive"))
      (node (ref "C46") (pin "2") (pinfunction "2_2") (pintype "passive"))
      (node (ref "C48") (pin "2") (pinfunction "2_2") (pintype "passive"))
      (node (ref "C49") (pin "-") (pinfunction "-_-") (pintype "passive"))
      (node (ref "C5") (pin "2") (pinfunction "2_2") (pintype "passive"))
      (node (ref "C50") (pin "-") (pinfunction "-_-") (pintype "passive"))
      (node (ref "C51") (pin "2") (pinfunction "2_2") (pintype "passive"))
      (node (ref "C52") (pin "2") (pinfunction "2_2") (pintype "passive"))
      (node (ref "C53") (pin "2") (pinfunction "2_2") (pintype "passive"))
      (node (ref "C54") (pin "2") (pinfunction "2_2") (pintype "passive"))
      (node (ref "C55") (pin "2") (pinfunction "2_2") (pintype "passive"))
      (node (ref "C56") (pin "2") (pinfunction "2_2") (pintype "passive"))
      (node (ref "C57") (pin "2") (pinfunction "2_2") (pintype "passive"))
      (node (ref "C58") (pin "2") (pinfunction "2_2") (pintype "passive"))
      (node (ref "C59") (pin "2") (pinfunction "2_2") (pintype "passive"))
      (node (ref "C6") (pin "2") (pinfunction "2_2") (pintype "passive"))
      (node (ref "C61") (pin "2") (pinfunction "2_2") (pintype "passive"))
      (node (ref "C62") (pin "2") (pinfunction "2_2") (pintype "passive"))
      (node (ref "C63") (pin "2") (pinfunction "2_2") (pintype "passive"))
      (node (ref "C64") (pin "2") (pinfunction "2_2") (pintype "passive"))
      (node (ref "C65") (pin "2") (pinfunction "2_2") (pintype "passive"))
      (node (ref "C66") (pin "2") (pinfunction "2_2") (pintype "passive"))
      (node (ref "C68") (pin "2") (pinfunction "2_2") (pintype "passive"))
      (node (ref "C69") (pin "2") (pinfunction "2_2") (pintype "passive"))
      (node (ref "C7") (pin "2") (pinfunction "2_2") (pintype "passive"))
      (node (ref "C70") (pin "2") (pinfunction "2_2") (pintype "passive"))
      (node (ref "C71") (pin "2") (pinfunction "2_2") (pintype "passive"))
      (node (ref "C73") (pin "2") (pinfunction "2_2") (pintype "passive"))
      (node (ref "C74") (pin "-") (pinfunction "-_-") (pintype "passive"))
      (node (ref "C75") (pin "-") (pinfunction "-_-") (pintype "passive"))
      (node (ref "C8") (pin "2") (pinfunction "2_2") (pintype "passive"))
      (node (ref "C9") (pin "-") (pinfunction "-_-") (pintype "passive"))
      (node (ref "D3") (pin "A") (pinfunction "ANODE_A") (pintype "passive"))
      (node (ref "D4") (pin "A") (pinfunction "ANODE_A") (pintype "passive"))
      (node (ref "D6") (pin "A") (pinfunction "ANODE_A") (pintype "passive"))
      (node (ref "J1") (pin "1") (pinfunction "1_1") (pintype "passive"))
      (node (ref "J3") (pin "1") (pinfunction "1_1") (pintype "passive"))
      (node (ref "J5") (pin "1") (pinfunction "1_1") (pintype "passive"))
      (node (ref "JP2") (pin "1") (pinfunction "1_1") (pintype "passive"))
      (node (ref "JP4") (pin "1") (pinfunction "1_1") (pintype "passive"))
      (node (ref "JP7") (pin "1") (pinfunction "1_1") (pintype "passive"))
      (node (ref "LED1") (pin "3-GND") (pinfunction "GND_3-GND") (pintype "bidirectional"))
      (node (ref "LED2") (pin "3-GND") (pinfunction "GND_3-GND") (pintype "bidirectional"))
      (node (ref "LED3") (pin "3-GND") (pinfunction "GND_3-GND") (pintype "bidirectional"))
      (node (ref "Q1") (pin "2") (pinfunction "S_2") (pintype "bidirectional"))
      (node (ref "Q11") (pin "3") (pinfunction "S_3") (pintype "bidirectional"))
      (node (ref "Q12") (pin "1") (pinfunction "S_1") (pintype "bidirectional"))
      (node (ref "Q12") (pin "2") (pinfunction "S_2") (pintype "bidirectional"))
      (node (ref "Q12") (pin "3") (pinfunction "S_3") (pintype "bidirectional"))
      (node (ref "Q13") (pin "1") (pinfunction "S_1") (pintype "bidirectional"))
      (node (ref "Q13") (pin "2") (pinfunction "S_2") (pintype "bidirectional"))
      (node (ref "Q13") (pin "3") (pinfunction "S_3") (pintype "bidirectional"))
      (node (ref "Q14") (pin "2") (pinfunction "S_2") (pintype "bidirectional"))
      (node (ref "Q3") (pin "1") (pinfunction "S_1") (pintype "bidirectional"))
      (node (ref "Q3") (pin "2") (pinfunction "S_2") (pintype "bidirectional"))
      (node (ref "Q3") (pin "3") (pinfunction "S_3") (pintype "bidirectional"))
      (node (ref "Q4") (pin "1") (pinfunction "S_1") (pintype "bidirectional"))
      (node (ref "Q4") (pin "2") (pinfunction "S_2") (pintype "bidirectional"))
      (node (ref "Q4") (pin "3") (pinfunction "S_3") (pintype "bidirectional"))
      (node (ref "Q5") (pin "3") (pinfunction "S_3") (pintype "bidirectional"))
      (node (ref "Q6") (pin "3") (pinfunction "S_3") (pintype "bidirectional"))
      (node (ref "Q7") (pin "1") (pinfunction "S_1") (pintype "bidirectional"))
      (node (ref "Q7") (pin "2") (pinfunction "S_2") (pintype "bidirectional"))
      (node (ref "Q7") (pin "3") (pinfunction "S_3") (pintype "bidirectional"))
      (node (ref "Q8") (pin "1") (pinfunction "S_1") (pintype "bidirectional"))
      (node (ref "Q8") (pin "2") (pinfunction "S_2") (pintype "bidirectional"))
      (node (ref "Q8") (pin "3") (pinfunction "S_3") (pintype "bidirectional"))
      (node (ref "Q9") (pin "2") (pinfunction "S_2") (pintype "bidirectional"))
      (node (ref "R100") (pin "1") (pinfunction "1_1") (pintype "passive"))
      (node (ref "R106") (pin "2") (pinfunction "2_2") (pintype "passive"))
      (node (ref "R107") (pin "2") (pinfunction "2_2") (pintype "passive"))
      (node (ref "R11") (pin "1") (pinfunction "1_1") (pintype "passive"))
      (node (ref "R111") (pin "2") (pinfunction "2_2") (pintype "passive"))
      (node (ref "R112") (pin "2") (pinfunction "2_2") (pintype "passive"))
      (node (ref "R115") (pin "2") (pinfunction "2_2") (pintype "passive"))
      (node (ref "R117") (pin "2") (pinfunction "2_2") (pintype "passive"))
      (node (ref "R119") (pin "1") (pinfunction "1_1") (pintype "passive"))
      (node (ref "R19") (pin "1") (pinfunction "1_1") (pintype "passive"))
      (node (ref "R20") (pin "2") (pinfunction "2_2") (pintype "passive"))
      (node (ref "R23") (pin "1") (pinfunction "1_1") (pintype "passive"))
      (node (ref "R25") (pin "2") (pinfunction "2_2") (pintype "passive"))
      (node (ref "R26") (pin "2") (pinfunction "2_2") (pintype "passive"))
      (node (ref "R27") (pin "2") (pinfunction "2_2") (pintype "passive"))
      (node (ref "R29") (pin "2") (pinfunction "2_2") (pintype "passive"))
      (node (ref "R3") (pin "2") (pinfunction "2_2") (pintype "passive"))
      (node (ref "R31") (pin "2") (pinfunction "2_2") (pintype "passive"))
      (node (ref "R34") (pin "2") (pinfunction "2_2") (pintype "passive"))
      (node (ref "R35") (pin "2") (pinfunction "2_2") (pintype "passive"))
      (node (ref "R37") (pin "1") (pinfunction "1_1") (pintype "passive"))
      (node (ref "R4") (pin "2") (pinfunction "2_2") (pintype "passive"))
      (node (ref "R42") (pin "2") (pinfunction "2_2") (pintype "passive"))
      (node (ref "R45") (pin "1") (pinfunction "1_1") (pintype "passive"))
      (node (ref "R50") (pin "2") (pinfunction "2_2") (pintype "passive"))
      (node (ref "R52") (pin "1") (pinfunction "1_1") (pintype "passive"))
      (node (ref "R55") (pin "1") (pinfunction "1_1") (pintype "passive"))
      (node (ref "R58") (pin "2") (pinfunction "2_2") (pintype "passive"))
      (node (ref "R59") (pin "2") (pinfunction "2_2") (pintype "passive"))
      (node (ref "R60") (pin "1") (pinfunction "1_1") (pintype "passive"))
      (node (ref "R66") (pin "2") (pinfunction "2_2") (pintype "passive"))
      (node (ref "R67") (pin "2") (pinfunction "2_2") (pintype "passive"))
      (node (ref "R71") (pin "2") (pinfunction "2_2") (pintype "passive"))
      (node (ref "R72") (pin "2") (pinfunction "2_2") (pintype "passive"))
      (node (ref "R75") (pin "2") (pinfunction "2_2") (pintype "passive"))
      (node (ref "R77") (pin "2") (pinfunction "2_2") (pintype "passive"))
      (node (ref "R79") (pin "1") (pinfunction "1_1") (pintype "passive"))
      (node (ref "R8") (pin "1") (pinfunction "1_1") (pintype "passive"))
      (node (ref "R82") (pin "2") (pinfunction "2_2") (pintype "passive"))
      (node (ref "R85") (pin "1") (pinfunction "1_1") (pintype "passive"))
      (node (ref "R90") (pin "2") (pinfunction "2_2") (pintype "passive"))
      (node (ref "R92") (pin "1") (pinfunction "1_1") (pintype "passive"))
      (node (ref "R95") (pin "1") (pinfunction "1_1") (pintype "passive"))
      (node (ref "R98") (pin "2") (pinfunction "2_2") (pintype "passive"))
      (node (ref "R99") (pin "2") (pinfunction "2_2") (pintype "passive"))
      (node (ref "T1") (pin "1") (pinfunction "1_1") (pintype "bidirectional"))
      (node (ref "T2") (pin "1") (pinfunction "1_1") (pintype "bidirectional"))
      (node (ref "T3") (pin "1") (pinfunction "1_1") (pintype "bidirectional"))
      (node (ref "U1") (pin "6") (pinfunction "PGND_6") (pintype "bidirectional"))
      (node (ref "U10") (pin "3") (pinfunction "A_3") (pintype "passive"))
      (node (ref "U11") (pin "6") (pinfunction "PGND_6") (pintype "bidirectional"))
      (node (ref "U12") (pin "2") (pinfunction "GND_2") (pintype "bidirectional"))
      (node (ref "U13") (pin "2") (pinfunction "VSS_2") (pintype "bidirectional"))
      (node (ref "U14") (pin "GND") (pinfunction "GND_GND") (pintype "bidirectional"))
      (node (ref "U14") (pin "GND2") (pinfunction "GND2_GND2") (pintype "bidirectional"))
      (node (ref "U14") (pin "GND4") (pinfunction "GND4_GND4") (pintype "bidirectional"))
      (node (ref "U15") (pin "2") (pinfunction "GND_2") (pintype "bidirectional"))
      (node (ref "U16") (pin "2") (pinfunction "VSS_2") (pintype "bidirectional"))
      (node (ref "U17") (pin "3") (pinfunction "A_3") (pintype "passive"))
      (node (ref "U18") (pin "6") (pinfunction "PGND_6") (pintype "bidirectional"))
      (node (ref "U19") (pin "2") (pinfunction "GND_2") (pintype "bidirectional"))
      (node (ref "U2") (pin "GND") (pinfunction "GND_GND") (pintype "bidirectional"))
      (node (ref "U2") (pin "GND2") (pinfunction "GND2_GND2") (pintype "bidirectional"))
      (node (ref "U2") (pin "GND4") (pinfunction "GND4_GND4") (pintype "bidirectional"))
      (node (ref "U20") (pin "2") (pinfunction "VSS_2") (pintype "bidirectional"))
      (node (ref "U21") (pin "GND") (pinfunction "GND_GND") (pintype "bidirectional"))
      (node (ref "U21") (pin "GND2") (pinfunction "GND2_GND2") (pintype "bidirectional"))
      (node (ref "U21") (pin "GND4") (pinfunction "GND4_GND4") (pintype "bidirectional"))
      (node (ref "U3") (pin "2") (pinfunction "GND_2") (pintype "bidirectional"))
      (node (ref "U4") (pin "2") (pinfunction "GND_2") (pintype "bidirectional"))
      (node (ref "U5") (pin "2") (pinfunction "VSS_2") (pintype "bidirectional"))
      (node (ref "U6") (pin "2") (pinfunction "GND_2") (pintype "bidirectional"))
      (node (ref "U7") (pin "2") (pinfunction "VSS_2") (pintype "bidirectional"))
      (node (ref "U8") (pin "2") (pinfunction "VSS_2") (pintype "bidirectional"))
      (node (ref "U9") (pin "3") (pinfunction "A_3") (pintype "passive"))
    )
    (net (code "22") (name "HSTH") (class "Default")
      (node (ref "C27") (pin "1") (pinfunction "1_1") (pintype "passive"))
      (node (ref "C41") (pin "1") (pinfunction "1_1") (pintype "passive"))
      (node (ref "C66") (pin "1") (pinfunction "1_1") (pintype "passive"))
      (node (ref "R108") (pin "1") (pinfunction "1_1") (pintype "passive"))
      (node (ref "R44") (pin "1") (pinfunction "1_1") (pintype "passive"))
      (node (ref "R68") (pin "1") (pinfunction "1_1") (pintype "passive"))
      (node (ref "T1") (pin "2") (pinfunction "2_2") (pintype "bidirectional"))
      (node (ref "T2") (pin "2") (pinfunction "2_2") (pintype "bidirectional"))
      (node (ref "T3") (pin "2") (pinfunction "2_2") (pintype "bidirectional"))
      (node (ref "U14") (pin "A2") (pinfunction "A2_A2") (pintype "bidirectional"))
      (node (ref "U2") (pin "A2") (pinfunction "A2_A2") (pintype "bidirectional"))
      (node (ref "U21") (pin "A2") (pinfunction "A2_A2") (pintype "bidirectional"))
    )
    (net (code "23") (name "ISNS_REF") (class "Default")
      (node (ref "C26") (pin "1") (pinfunction "1_1") (pintype "passive"))
      (node (ref "C37") (pin "1") (pinfunction "1_1") (pintype "passive"))
      (node (ref "C5") (pin "1") (pinfunction "1_1") (pintype "passive"))
      (node (ref "C51") (pin "1") (pinfunction "1_1") (pintype "passive"))
      (node (ref "C6") (pin "1") (pinfunction "1_1") (pintype "passive"))
      (node (ref "C62") (pin "1") (pinfunction "1_1") (pintype "passive"))
      (node (ref "R2") (pin "2") (pinfunction "2_2") (pintype "passive"))
      (node (ref "R3") (pin "1") (pinfunction "1_1") (pintype "passive"))
      (node (ref "R30") (pin "2") (pinfunction "2_2") (pintype "passive"))
      (node (ref "R31") (pin "1") (pinfunction "1_1") (pintype "passive"))
      (node (ref "R81") (pin "2") (pinfunction "2_2") (pintype "passive"))
      (node (ref "R82") (pin "1") (pinfunction "1_1") (pintype "passive"))
      (node (ref "TP1") (pin "1") (pinfunction "1_1") (pintype "bidirectional"))
      (node (ref "TP4") (pin "1") (pinfunction "1_1") (pintype "bidirectional"))
      (node (ref "TP5") (pin "1") (pinfunction "1_1") (pintype "bidirectional"))
      (node (ref "U14") (pin "A5") (pinfunction "A5_A5") (pintype "bidirectional"))
      (node (ref "U15") (pin "1") (pinfunction "REF_1") (pintype "bidirectional"))
      (node (ref "U2") (pin "A5") (pinfunction "A5_A5") (pintype "bidirectional"))
      (node (ref "U21") (pin "A5") (pinfunction "A5_A5") (pintype "bidirectional"))
      (node (ref "U3") (pin "1") (pinfunction "REF_1") (pintype "bidirectional"))
      (node (ref "U6") (pin "1") (pinfunction "REF_1") (pintype "bidirectional"))
    )
    (net (code "24") (name "NGATE1") (class "Default")
      (node (ref "Q12") (pin "4") (pinfunction "G_4") (pintype "bidirectional"))
      (node (ref "Q3") (pin "4") (pinfunction "G_4") (pintype "bidirectional"))
      (node (ref "Q7") (pin "4") (pinfunction "G_4") (pintype "bidirectional"))
      (node (ref "R4") (pin "1") (pinfunction "1_1") (pintype "passive"))
      (node (ref "R58") (pin "1") (pinfunction "1_1") (pintype "passive"))
      (node (ref "R98") (pin "1") (pinfunction "1_1") (pintype "passive"))
      (node (ref "U1") (pin "5") (pinfunction "DRVL_5") (pintype "bidirectional"))
      (node (ref "U11") (pin "5") (pinfunction "DRVL_5") (pintype "bidirectional"))
      (node (ref "U18") (pin "5") (pinfunction "DRVL_5") (pintype "bidirectional"))
    )
    (net (code "25") (name "Net-(C24-Pad1)") (class "Default")
      (node (ref "C24") (pin "1") (pinfunction "1_1") (pintype "passive"))
      (node (ref "R39") (pin "2") (pinfunction "2_2") (pintype "passive"))
    )
    (net (code "26") (name "Net-(C35-Pad1)") (class "Default")
      (node (ref "C35") (pin "1") (pinfunction "1_1") (pintype "passive"))
      (node (ref "R61") (pin "2") (pinfunction "2_2") (pintype "passive"))
    )
    (net (code "27") (name "Net-(C60-Pad1)") (class "Default")
      (node (ref "C60") (pin "1") (pinfunction "1_1") (pintype "passive"))
      (node (ref "R101") (pin "2") (pinfunction "2_2") (pintype "passive"))
    )
    (net (code "28") (name "Net-(D1-CATHODE)") (class "Default")
      (node (ref "C2") (pin "1") (pinfunction "1_1") (pintype "passive"))
      (node (ref "D1") (pin "K") (pinfunction "CATHODE_K") (pintype "passive"))
      (node (ref "U1") (pin "1") (pinfunction "BST_1") (pintype "bidirectional"))
    )
    (net (code "29") (name "Net-(D2-CATHODE)") (class "Default")
      (node (ref "C42") (pin "1") (pinfunction "1_1") (pintype "passive"))
      (node (ref "D2") (pin "K") (pinfunction "CATHODE_K") (pintype "passive"))
      (node (ref "U11") (pin "1") (pinfunction "BST_1") (pintype "bidirectional"))
    )
    (net (code "30") (name "Net-(D3-CATHODE)") (class "Default")
      (node (ref "C47") (pin "2") (pinfunction "2_2") (pintype "passive"))
      (node (ref "D3") (pin "K") (pinfunction "CATHODE_K") (pintype "passive"))
      (node (ref "L4") (pin "1") (pinfunction "P$1_1") (pintype "passive"))
      (node (ref "U12") (pin "6") (pinfunction "SW_6") (pintype "bidirectional"))
    )
    (net (code "31") (name "Net-(D4-CATHODE)") (class "Default")
      (node (ref "C13") (pin "2") (pinfunction "2_2") (pintype "passive"))
      (node (ref "D4") (pin "K") (pinfunction "CATHODE_K") (pintype "passive"))
      (node (ref "L2") (pin "1") (pinfunction "P$1_1") (pintype "passive"))
      (node (ref "U4") (pin "6") (pinfunction "SW_6") (pintype "bidirectional"))
    )
    (net (code "32") (name "Net-(D5-CATHODE)") (class "Default")
      (node (ref "C67") (pin "1") (pinfunction "1_1") (pintype "passive"))
      (node (ref "D5") (pin "K") (pinfunction "CATHODE_K") (pintype "passive"))
      (node (ref "U18") (pin "1") (pinfunction "BST_1") (pintype "bidirectional"))
    )
    (net (code "33") (name "Net-(D6-CATHODE)") (class "Default")
      (node (ref "C72") (pin "2") (pinfunction "2_2") (pintype "passive"))
      (node (ref "D6") (pin "K") (pinfunction "CATHODE_K") (pintype "passive"))
      (node (ref "L6") (pin "1") (pinfunction "P$1_1") (pintype "passive"))
      (node (ref "U19") (pin "6") (pinfunction "SW_6") (pintype "bidirectional"))
    )
    (net (code "34") (name "Net-(F1-1)") (class "Default")
      (node (ref "F1") (pin "A") (pinfunction "1_A") (pintype "bidirectional"))
      (node (ref "Q4") (pin "5") (pinfunction "D_5") (pintype "bidirectional"))
      (node (ref "Q4") (pin "6") (pinfunction "D_6") (pintype "bidirectional"))
      (node (ref "Q4") (pin "7") (pinfunction "D_7") (pintype "bidirectional"))
      (node (ref "Q4") (pin "8") (pinfunction "D_8") (pintype "bidirectional"))
    )
    (net (code "35") (name "Net-(F3-1)") (class "Default")
      (node (ref "F3") (pin "A") (pinfunction "1_A") (pintype "bidirectional"))
      (node (ref "Q8") (pin "5") (pinfunction "D_5") (pintype "bidirectional"))
      (node (ref "Q8") (pin "6") (pinfunction "D_6") (pintype "bidirectional"))
      (node (ref "Q8") (pin "7") (pinfunction "D_7") (pintype "bidirectional"))
      (node (ref "Q8") (pin "8") (pinfunction "D_8") (pintype "bidirectional"))
    )
    (net (code "36") (name "Net-(F5-1)") (class "Default")
      (node (ref "F5") (pin "A") (pinfunction "1_A") (pintype "bidirectional"))
      (node (ref "Q13") (pin "5") (pinfunction "D_5") (pintype "bidirectional"))
      (node (ref "Q13") (pin "6") (pinfunction "D_6") (pintype "bidirectional"))
      (node (ref "Q13") (pin "7") (pinfunction "D_7") (pintype "bidirectional"))
      (node (ref "Q13") (pin "8") (pinfunction "D_8") (pintype "bidirectional"))
    )
    (net (code "37") (name "Net-(J1-Pad2)") (class "Default")
      (node (ref "J1") (pin "2") (pinfunction "2_2") (pintype "passive"))
      (node (ref "R6") (pin "1") (pinfunction "1_1") (pintype "passive"))
    )
    (net (code "38") (name "Net-(J3-Pad2)") (class "Default")
      (node (ref "J3") (pin "2") (pinfunction "2_2") (pintype "passive"))
      (node (ref "R53") (pin "1") (pinfunction "1_1") (pintype "passive"))
    )
    (net (code "39") (name "Net-(J5-Pad2)") (class "Default")
      (node (ref "J5") (pin "2") (pinfunction "2_2") (pintype "passive"))
      (node (ref "R93") (pin "1") (pinfunction "1_1") (pintype "passive"))
    )
    (net (code "40") (name "Net-(LED1-DIN)") (class "Default")
      (node (ref "LED1") (pin "4-DIN") (pinfunction "DIN_4-DIN") (pintype "input"))
      (node (ref "Q1") (pin "3") (pinfunction "D_3") (pintype "bidirectional"))
      (node (ref "R1") (pin "2") (pinfunction "2_2") (pintype "passive"))
    )
    (net (code "41") (name "Net-(LED2-DIN)") (class "Default")
      (node (ref "LED2") (pin "4-DIN") (pinfunction "DIN_4-DIN") (pintype "input"))
      (node (ref "Q9") (pin "3") (pinfunction "D_3") (pintype "bidirectional"))
      (node (ref "R73") (pin "2") (pinfunction "2_2") (pintype "passive"))
    )
    (net (code "42") (name "Net-(LED3-DIN)") (class "Default")
      (node (ref "LED3") (pin "4-DIN") (pinfunction "DIN_4-DIN") (pintype "input"))
      (node (ref "Q14") (pin "3") (pinfunction "D_3") (pintype "bidirectional"))
      (node (ref "R113") (pin "2") (pinfunction "2_2") (pintype "passive"))
    )
    (net (code "43") (name "Net-(Q5-D)") (class "Default")
      (node (ref "F2") (pin "1") (pinfunction "1_1") (pintype "bidirectional"))
      (node (ref "Q5") (pin "2") (pinfunction "D_2") (pintype "bidirectional"))
    )
    (net (code "44") (name "Net-(Q5-G)") (class "Default")
      (node (ref "Q5") (pin "1") (pinfunction "G_1") (pintype "bidirectional"))
      (node (ref "R40") (pin "1") (pinfunction "1_1") (pintype "passive"))
    )
    (net (code "45") (name "Net-(Q6-D)") (class "Default")
      (node (ref "F4") (pin "1") (pinfunction "1_1") (pintype "bidirectional"))
      (node (ref "Q6") (pin "2") (pinfunction "D_2") (pintype "bidirectional"))
    )
    (net (code "46") (name "Net-(Q6-G)") (class "Default")
      (node (ref "Q6") (pin "1") (pinfunction "G_1") (pintype "bidirectional"))
      (node (ref "R56") (pin "1") (pinfunction "1_1") (pintype "passive"))
    )
    (net (code "47") (name "Net-(Q11-D)") (class "Default")
      (node (ref "F6") (pin "1") (pinfunction "1_1") (pintype "bidirectional"))
      (node (ref "Q11") (pin "2") (pinfunction "D_2") (pintype "bidirectional"))
    )
    (net (code "48") (name "Net-(Q11-G)") (class "Default")
      (node (ref "Q11") (pin "1") (pinfunction "G_1") (pintype "bidirectional"))
      (node (ref "R96") (pin "1") (pinfunction "1_1") (pintype "passive"))
    )
    (net (code "49") (name "Net-(U2-A12{slash}D+)") (class "Default")
      (node (ref "R38") (pin "2") (pinfunction "2_2") (pintype "passive"))
      (node (ref "U2") (pin "A12") (pinfunction "A12/D+_A12") (pintype "bidirectional"))
    )
    (net (code "50") (name "Net-(U3-IN-)") (class "Default")
      (node (ref "C10") (pin "1") (pinfunction "1_1") (pintype "passive"))
      (node (ref "C9") (pin "+") (pinfunction "+_+") (pintype "passive"))
      (node (ref "L1") (pin "P$2") (pinfunction "P$2_P$2") (pintype "passive"))
      (node (ref "R12") (pin "1") (pinfunction "1_1") (pintype "passive"))
      (node (ref "U3") (pin "5") (pinfunction "IN-_5") (pintype "bidirectional"))
    )
    (net (code "51") (name "Net-(U3-OUT)") (class "Default")
      (node (ref "R9") (pin "1") (pinfunction "1_1") (pintype "passive"))
      (node (ref "U3") (pin "6") (pinfunction "OUT_6") (pintype "bidirectional"))
    )
    (net (code "52") (name "Net-(U4-BST)") (class "Default")
      (node (ref "C13") (pin "1") (pinfunction "1_1") (pintype "passive"))
      (node (ref "U4") (pin "1") (pinfunction "BST_1") (pintype "bidirectional"))
    )
    (net (code "53") (name "Net-(U4-EN)") (class "Default")
      (node (ref "R21") (pin "1") (pinfunction "1_1") (pintype "passive"))
      (node (ref "U4") (pin "4") (pinfunction "EN_4") (pintype "bidirectional"))
    )
    (net (code "54") (name "Net-(U4-FB)") (class "Default")
      (node (ref "R22") (pin "1") (pinfunction "1_1") (pintype "passive"))
      (node (ref "R23") (pin "2") (pinfunction "2_2") (pintype "passive"))
      (node (ref "U4") (pin "3") (pinfunction "FB_3") (pintype "bidirectional"))
    )
    (net (code "55") (name "Net-(U5-VIN+)") (class "Default")
      (node (ref "R15") (pin "2") (pinfunction "2_2") (pintype "passive"))
      (node (ref "R19") (pin "2") (pinfunction "2_2") (pintype "passive"))
      (node (ref "U5") (pin "1") (pinfunction "VIN+_1") (pintype "bidirectional"))
    )
    (net (code "56") (name "Net-(U5-VIN-)") (class "Default")
      (node (ref "R14") (pin "2") (pinfunction "2_2") (pintype "passive"))
      (node (ref "R18") (pin "1") (pinfunction "1_1") (pintype "passive"))
      (node (ref "U5") (pin "3") (pinfunction "VIN-_3") (pintype "bidirectional"))
    )
    (net (code "57") (name "Net-(U5-VOUT)") (class "Default")
      (node (ref "R18") (pin "2") (pinfunction "2_2") (pintype "passive"))
      (node (ref "R24") (pin "1") (pinfunction "1_1") (pintype "passive"))
      (node (ref "U5") (pin "4") (pinfunction "VOUT_4") (pintype "bidirectional"))
    )
    (net (code "58") (name "Net-(U6-IN-)") (class "Default")
      (node (ref "C31") (pin "1") (pinfunction "1_1") (pintype "passive"))
      (node (ref "C50") (pin "+") (pinfunction "+_+") (pintype "passive"))
      (node (ref "L3") (pin "P$2") (pinfunction "P$2_P$2") (pintype "passive"))
      (node (ref "R76") (pin "1") (pinfunction "1_1") (pintype "passive"))
      (node (ref "U6") (pin "5") (pinfunction "IN-_5") (pintype "bidirectional"))
    )
    (net (code "59") (name "Net-(U6-OUT)") (class "Default")
      (node (ref "R32") (pin "1") (pinfunction "1_1") (pintype "passive"))
      (node (ref "U6") (pin "6") (pinfunction "OUT_6") (pintype "bidirectional"))
    )
    (net (code "60") (name "Net-(U7-VIN+)") (class "Default")
      (node (ref "R28") (pin "2") (pinfunction "2_2") (pintype "passive"))
      (node (ref "R29") (pin "1") (pinfunction "1_1") (pintype "passive"))
      (node (ref "U7") (pin "1") (pinfunction "VIN+_1") (pintype "bidirectional"))
    )
    (net (code "61") (name "Net-(U7-VIN-)") (class "Default")
      (node (ref "C19") (pin "1") (pinfunction "1_1") (pintype "passive"))
      (node (ref "R36") (pin "2") (pinfunction "2_2") (pintype "passive"))
      (node (ref "R37") (pin "2") (pinfunction "2_2") (pintype "passive"))
      (node (ref "R39") (pin "1") (pinfunction "1_1") (pintype "passive"))
      (node (ref "U7") (pin "3") (pinfunction "VIN-_3") (pintype "bidirectional"))
    )
    (net (code "62") (name "Net-(U8-VIN+)") (class "Default")
      (node (ref "R41") (pin "2") (pinfunction "2_2") (pintype "passive"))
      (node (ref "R45") (pin "2") (pinfunction "2_2") (pintype "passive"))
      (node (ref "U8") (pin "1") (pinfunction "VIN+_1") (pintype "bidirectional"))
    )
    (net (code "63") (name "Net-(U8-VIN-)") (class "Default")
      (node (ref "R46") (pin "2") (pinfunction "2_2") (pintype "passive"))
      (node (ref "R47") (pin "1") (pinfunction "1_1") (pintype "passive"))
      (node (ref "U8") (pin "3") (pinfunction "VIN-_3") (pintype "bidirectional"))
    )
    (net (code "64") (name "Net-(U8-VOUT)") (class "Default")
      (node (ref "R47") (pin "2") (pinfunction "2_2") (pintype "passive"))
      (node (ref "R74") (pin "1") (pinfunction "1_1") (pintype "passive"))
      (node (ref "U8") (pin "4") (pinfunction "VOUT_4") (pintype "bidirectional"))
    )
    (net (code "65") (name "Net-(U12-BST)") (class "Default")
      (node (ref "C47") (pin "1") (pinfunction "1_1") (pintype "passive"))
      (node (ref "U12") (pin "1") (pinfunction "BST_1") (pintype "bidirectional"))
    )
    (net (code "66") (name "Net-(U12-EN)") (class "Default")
      (node (ref "R80") (pin "1") (pinfunction "1_1") (pintype "passive"))
      (node (ref "U12") (pin "4") (pinfunction "EN_4") (pintype "bidirectional"))
    )
    (net (code "67") (name "Net-(U12-FB)") (class "Default")
      (node (ref "R78") (pin "1") (pinfunction "1_1") (pintype "passive"))
      (node (ref "R79") (pin "2") (pinfunction "2_2") (pintype "passive"))
      (node (ref "U12") (pin "3") (pinfunction "FB_3") (pintype "bidirectional"))
    )
    (net (code "68") (name "Net-(U13-VIN+)") (class "Default")
      (node (ref "R59") (pin "1") (pinfunction "1_1") (pintype "passive"))
      (node (ref "R62") (pin "2") (pinfunction "2_2") (pintype "passive"))
      (node (ref "U13") (pin "1") (pinfunction "VIN+_1") (pintype "bidirectional"))
    )
    (net (code "69") (name "Net-(U13-VIN-)") (class "Default")
      (node (ref "C48") (pin "1") (pinfunction "1_1") (pintype "passive"))
      (node (ref "R60") (pin "2") (pinfunction "2_2") (pintype "passive"))
      (node (ref "R61") (pin "1") (pinfunction "1_1") (pintype "passive"))
      (node (ref "R63") (pin "2") (pinfunction "2_2") (pintype "passive"))
      (node (ref "U13") (pin "3") (pinfunction "VIN-_3") (pintype "bidirectional"))
    )
    (net (code "70") (name "Net-(U14-A12{slash}D+)") (class "Default")
      (node (ref "R65") (pin "2") (pinfunction "2_2") (pintype "passive"))
      (node (ref "U14") (pin "A12") (pinfunction "A12/D+_A12") (pintype "bidirectional"))
    )
    (net (code "71") (name "Net-(U15-IN-)") (class "Default")
      (node (ref "C56") (pin "1") (pinfunction "1_1") (pintype "passive"))
      (node (ref "C75") (pin "+") (pinfunction "+_+") (pintype "passive"))
      (node (ref "L5") (pin "P$2") (pinfunction "P$2_P$2") (pintype "passive"))
      (node (ref "R116") (pin "1") (pinfunction "1_1") (pintype "passive"))
      (node (ref "U15") (pin "5") (pinfunction "IN-_5") (pintype "bidirectional"))
    )
    (net (code "72") (name "Net-(U15-OUT)") (class "Default")
      (node (ref "R83") (pin "1") (pinfunction "1_1") (pintype "passive"))
      (node (ref "U15") (pin "6") (pinfunction "OUT_6") (pintype "bidirectional"))
    )
    (net (code "73") (name "Net-(U16-VIN+)") (class "Default")
      (node (ref "R84") (pin "2") (pinfunction "2_2") (pintype "passive"))
      (node (ref "R85") (pin "2") (pinfunction "2_2") (pintype "passive"))
      (node (ref "U16") (pin "1") (pinfunction "VIN+_1") (pintype "bidirectional"))
    )
    (net (code "74") (name "Net-(U16-VIN-)") (class "Default")
      (node (ref "R86") (pin "2") (pinfunction "2_2") (pintype "passive"))
      (node (ref "R87") (pin "1") (pinfunction "1_1") (pintype "passive"))
      (node (ref "U16") (pin "3") (pinfunction "VIN-_3") (pintype "bidirectional"))
    )
    (net (code "75") (name "Net-(U16-VOUT)") (class "Default")
      (node (ref "R114") (pin "1") (pinfunction "1_1") (pintype "passive"))
      (node (ref "R87") (pin "2") (pinfunction "2_2") (pintype "passive"))
      (node (ref "U16") (pin "4") (pinfunction "VOUT_4") (pintype "bidirectional"))
    )
    (net (code "76") (name "Net-(U19-BST)") (class "Default")
      (node (ref "C72") (pin "1") (pinfunction "1_1") (pintype "passive"))
      (node (ref "U19") (pin "1") (pinfunction "BST_1") (pintype "bidirectional"))
    )
    (net (code "77") (name "Net-(U19-EN)") (class "Default")
      (node (ref "R120") (pin "1") (pinfunction "1_1") (pintype "passive"))
      (node (ref "U19") (pin "4") (pinfunction "EN_4") (pintype "bidirectional"))
    )
    (net (code "78") (name "Net-(U19-FB)") (class "Default")
      (node (ref "R118") (pin "1") (pinfunction "1_1") (pintype "passive"))
      (node (ref "R119") (pin "2") (pinfunction "2_2") (pintype "passive"))
      (node (ref "U19") (pin "3") (pinfunction "FB_3") (pintype "bidirectional"))
    )
    (net (code "79") (name "Net-(U20-VIN+)") (class "Default")
      (node (ref "R102") (pin "2") (pinfunction "2_2") (pintype "passive"))
      (node (ref "R99") (pin "1") (pinfunction "1_1") (pintype "passive"))
      (node (ref "U20") (pin "1") (pinfunction "VIN+_1") (pintype "bidirectional"))
    )
    (net (code "80") (name "Net-(U20-VIN-)") (class "Default")
      (node (ref "C73") (pin "1") (pinfunction "1_1") (pintype "passive"))
      (node (ref "R100") (pin "2") (pinfunction "2_2") (pintype "passive"))
      (node (ref "R101") (pin "1") (pinfunction "1_1") (pintype "passive"))
      (node (ref "R103") (pin "2") (pinfunction "2_2") (pintype "passive"))
      (node (ref "U20") (pin "3") (pinfunction "VIN-_3") (pintype "bidirectional"))
    )
    (net (code "81") (name "Net-(U21-A12{slash}D+)") (class "Default")
      (node (ref "R105") (pin "2") (pinfunction "2_2") (pintype "passive"))
      (node (ref "U21") (pin "A12") (pinfunction "A12/D+_A12") (pintype "bidirectional"))
    )
    (net (code "82") (name "OA1+") (class "Default")
      (node (ref "J2") (pin "2") (pinfunction "2_2") (pintype "passive"))
      (node (ref "J4") (pin "2") (pinfunction "2_2") (pintype "passive"))
      (node (ref "J6") (pin "2") (pinfunction "2_2") (pintype "passive"))
      (node (ref "R110") (pin "1") (pinfunction "1_1") (pintype "passive"))
      (node (ref "R15") (pin "1") (pinfunction "1_1") (pintype "passive"))
      (node (ref "R17") (pin "1") (pinfunction "1_1") (pintype "passive"))
      (node (ref "R41") (pin "1") (pinfunction "1_1") (pintype "passive"))
      (node (ref "R70") (pin "1") (pinfunction "1_1") (pintype "passive"))
      (node (ref "R84") (pin "1") (pinfunction "1_1") (pintype "passive"))
    )
    (net (code "83") (name "OA1-") (class "Default")
      (node (ref "J2") (pin "1") (pinfunction "1_1") (pintype "passive"))
      (node (ref "J4") (pin "1") (pinfunction "1_1") (pintype "passive"))
      (node (ref "J6") (pin "1") (pinfunction "1_1") (pintype "passive"))
      (node (ref "R109") (pin "1") (pinfunction "1_1") (pintype "passive"))
      (node (ref "R13") (pin "1") (pinfunction "1_1") (pintype "passive"))
      (node (ref "R14") (pin "1") (pinfunction "1_1") (pintype "passive"))
      (node (ref "R46") (pin "1") (pinfunction "1_1") (pintype "passive"))
      (node (ref "R69") (pin "1") (pinfunction "1_1") (pintype "passive"))
      (node (ref "R86") (pin "1") (pinfunction "1_1") (pintype "passive"))
    )
    (net (code "84") (name "PB5") (class "Default")
      (node (ref "JP1") (pin "3") (pinfunction "3_3") (pintype "passive"))
      (node (ref "JP5") (pin "3") (pinfunction "3_3") (pintype "passive"))
      (node (ref "JP8") (pin "3") (pinfunction "3_3") (pintype "passive"))
      (node (ref "R111") (pin "1") (pinfunction "1_1") (pintype "passive"))
      (node (ref "R35") (pin "1") (pinfunction "1_1") (pintype "passive"))
      (node (ref "R71") (pin "1") (pinfunction "1_1") (pintype "passive"))
      (node (ref "U14") (pin "B5") (pinfunction "B5_B5") (pintype "bidirectional"))
      (node (ref "U2") (pin "B5") (pinfunction "B5_B5") (pintype "bidirectional"))
      (node (ref "U21") (pin "B5") (pinfunction "B5_B5") (pintype "bidirectional"))
    )
    (net (code "85") (name "PB12") (class "Default")
      (node (ref "R117") (pin "1") (pinfunction "1_1") (pintype "passive"))
      (node (ref "R34") (pin "1") (pinfunction "1_1") (pintype "passive"))
      (node (ref "R77") (pin "1") (pinfunction "1_1") (pintype "passive"))
      (node (ref "U14") (pin "B12") (pinfunction "B12_B12") (pintype "bidirectional"))
      (node (ref "U2") (pin "B12") (pinfunction "B12_B12") (pintype "bidirectional"))
      (node (ref "U21") (pin "B12") (pinfunction "B12_B12") (pintype "bidirectional"))
    )
    (net (code "86") (name "PGATE1") (class "Default")
      (node (ref "Q10") (pin "4") (pinfunction "G_4") (pintype "bidirectional"))
      (node (ref "Q15") (pin "4") (pinfunction "G_4") (pintype "bidirectional"))
      (node (ref "Q2") (pin "4") (pinfunction "G_4") (pintype "bidirectional"))
      (node (ref "R5") (pin "2") (pinfunction "2_2") (pintype "passive"))
      (node (ref "R57") (pin "2") (pinfunction "2_2") (pintype "passive"))
      (node (ref "R97") (pin "2") (pinfunction "2_2") (pintype "passive"))
      (node (ref "U1") (pin "8") (pinfunction "DRVH_8") (pintype "bidirectional"))
      (node (ref "U11") (pin "8") (pinfunction "DRVH_8") (pintype "bidirectional"))
      (node (ref "U18") (pin "8") (pinfunction "DRVH_8") (pintype "bidirectional"))
    )
    (net (code "87") (name "SCL-TX") (class "Default")
      (node (ref "JP2") (pin "2") (pinfunction "2_2") (pintype "passive"))
      (node (ref "JP4") (pin "2") (pinfunction "2_2") (pintype "passive"))
      (node (ref "JP7") (pin "2") (pinfunction "2_2") (pintype "passive"))
      (node (ref "U14") (pin "B10") (pinfunction "B10_B10") (pintype "bidirectional"))
      (node (ref "U2") (pin "B10") (pinfunction "B10_B10") (pintype "bidirectional"))
      (node (ref "U21") (pin "B10") (pinfunction "B10_B10") (pintype "bidirectional"))
    )
    (net (code "88") (name "SDA-RX") (class "Default")
      (node (ref "JP2") (pin "3") (pinfunction "3_3") (pintype "passive"))
      (node (ref "JP4") (pin "3") (pinfunction "3_3") (pintype "passive"))
      (node (ref "JP7") (pin "3") (pinfunction "3_3") (pintype "passive"))
      (node (ref "U14") (pin "B11") (pinfunction "B11_B11") (pintype "bidirectional"))
      (node (ref "U2") (pin "B11") (pinfunction "B11_B11") (pintype "bidirectional"))
      (node (ref "U21") (pin "B11") (pinfunction "B11_B11") (pintype "bidirectional"))
    )
    (net (code "89") (name "unconnected-(U2-PadA0)") (class "Default")
      (node (ref "U2") (pin "A0") (pinfunction "A0_A0") (pintype "bidirectional"))
    )
    (net (code "90") (name "unconnected-(U2-PadA6)") (class "Default")
      (node (ref "U2") (pin "A6") (pinfunction "A6_A6") (pintype "bidirectional"))
    )
    (net (code "91") (name "unconnected-(U2-PadA7)") (class "Default")
      (node (ref "U2") (pin "A7") (pinfunction "A7_A7") (pintype "bidirectional"))
    )
    (net (code "92") (name "unconnected-(U2-PadA10)") (class "Default")
      (node (ref "U2") (pin "A10") (pinfunction "A10_A10") (pintype "bidirectional"))
    )
    (net (code "93") (name "unconnected-(U2-PadA15)") (class "Default")
      (node (ref "U2") (pin "A15") (pinfunction "A15_A15") (pintype "bidirectional"))
    )
    (net (code "94") (name "unconnected-(U2-PadB3)") (class "Default")
      (node (ref "U2") (pin "B3") (pinfunction "B3_B3") (pintype "bidirectional"))
    )
    (net (code "95") (name "unconnected-(U2-PadB6)") (class "Default")
      (node (ref "U2") (pin "B6") (pinfunction "B6_B6") (pintype "bidirectional"))
    )
    (net (code "96") (name "unconnected-(U2-PadB7)") (class "Default")
      (node (ref "U2") (pin "B7") (pinfunction "B7_B7") (pintype "bidirectional"))
    )
    (net (code "97") (name "unconnected-(U2-PadB8)") (class "Default")
      (node (ref "U2") (pin "B8") (pinfunction "B8_B8") (pintype "bidirectional"))
    )
    (net (code "98") (name "unconnected-(U2-PadB9)") (class "Default")
      (node (ref "U2") (pin "B9") (pinfunction "B9_B9") (pintype "bidirectional"))
    )
    (net (code "99") (name "unconnected-(U2-PadB15)") (class "Default")
      (node (ref "U2") (pin "B15") (pinfunction "B15_B15") (pintype "bidirectional"))
    )
    (net (code "100") (name "unconnected-(U2-PadRST)") (class "Default")
      (node (ref "U2") (pin "RST") (pinfunction "RST_RST") (pintype "bidirectional"))
    )
    (net (code "101") (name "unconnected-(U14-PadA0)") (class "Default")
      (node (ref "U14") (pin "A0") (pinfunction "A0_A0") (pintype "bidirectional"))
    )
    (net (code "102") (name "unconnected-(U14-PadA6)") (class "Default")
      (node (ref "U14") (pin "A6") (pinfunction "A6_A6") (pintype "bidirectional"))
    )
    (net (code "103") (name "unconnected-(U14-PadA7)") (class "Default")
      (node (ref "U14") (pin "A7") (pinfunction "A7_A7") (pintype "bidirectional"))
    )
    (net (code "104") (name "unconnected-(U14-PadA10)") (class "Default")
      (node (ref "U14") (pin "A10") (pinfunction "A10_A10") (pintype "bidirectional"))
    )
    (net (code "105") (name "unconnected-(U14-PadA15)") (class "Default")
      (node (ref "U14") (pin "A15") (pinfunction "A15_A15") (pintype "bidirectional"))
    )
    (net (code "106") (name "unconnected-(U14-PadB3)") (class "Default")
      (node (ref "U14") (pin "B3") (pinfunction "B3_B3") (pintype "bidirectional"))
    )
    (net (code "107") (name "unconnected-(U14-PadB6)") (class "Default")
      (node (ref "U14") (pin "B6") (pinfunction "B6_B6") (pintype "bidirectional"))
    )
    (net (code "108") (name "unconnected-(U14-PadB7)") (class "Default")
      (node (ref "U14") (pin "B7") (pinfunction "B7_B7") (pintype "bidirectional"))
    )
    (net (code "109") (name "unconnected-(U14-PadB8)") (class "Default")
      (node (ref "U14") (pin "B8") (pinfunction "B8_B8") (pintype "bidirectional"))
    )
    (net (code "110") (name "unconnected-(U14-PadB9)") (class "Default")
      (node (ref "U14") (pin "B9") (pinfunction "B9_B9") (pintype "bidirectional"))
    )
    (net (code "111") (name "unconnected-(U14-PadB15)") (class "Default")
      (node (ref "U14") (pin "B15") (pinfunction "B15_B15") (pintype "bidirectional"))
    )
    (net (code "112") (name "unconnected-(U14-PadRST)") (class "Default")
      (node (ref "U14") (pin "RST") (pinfunction "RST_RST") (pintype "bidirectional"))
    )
    (net (code "113") (name "unconnected-(U21-PadA0)") (class "Default")
      (node (ref "U21") (pin "A0") (pinfunction "A0_A0") (pintype "bidirectional"))
    )
    (net (code "114") (name "unconnected-(U21-PadA6)") (class "Default")
      (node (ref "U21") (pin "A6") (pinfunction "A6_A6") (pintype "bidirectional"))
    )
    (net (code "115") (name "unconnected-(U21-PadA7)") (class "Default")
      (node (ref "U21") (pin "A7") (pinfunction "A7_A7") (pintype "bidirectional"))
    )
    (net (code "116") (name "unconnected-(U21-PadA10)") (class "Default")
      (node (ref "U21") (pin "A10") (pinfunction "A10_A10") (pintype "bidirectional"))
    )
    (net (code "117") (name "unconnected-(U21-PadA15)") (class "Default")
      (node (ref "U21") (pin "A15") (pinfunction "A15_A15") (pintype "bidirectional"))
    )
    (net (code "118") (name "unconnected-(U21-PadB3)") (class "Default")
      (node (ref "U21") (pin "B3") (pinfunction "B3_B3") (pintype "bidirectional"))
    )
    (net (code "119") (name "unconnected-(U21-PadB6)") (class "Default")
      (node (ref "U21") (pin "B6") (pinfunction "B6_B6") (pintype "bidirectional"))
    )
    (net (code "120") (name "unconnected-(U21-PadB7)") (class "Default")
      (node (ref "U21") (pin "B7") (pinfunction "B7_B7") (pintype "bidirectional"))
    )
    (net (code "121") (name "unconnected-(U21-PadB8)") (class "Default")
      (node (ref "U21") (pin "B8") (pinfunction "B8_B8") (pintype "bidirectional"))
    )
    (net (code "122") (name "unconnected-(U21-PadB9)") (class "Default")
      (node (ref "U21") (pin "B9") (pinfunction "B9_B9") (pintype "bidirectional"))
    )
    (net (code "123") (name "unconnected-(U21-PadB15)") (class "Default")
      (node (ref "U21") (pin "B15") (pinfunction "B15_B15") (pintype "bidirectional"))
    )
    (net (code "124") (name "unconnected-(U21-PadRST)") (class "Default")
      (node (ref "U21") (pin "RST") (pinfunction "RST_RST") (pintype "bidirectional"))
    )
  )
)
